# PT_2015_PB_MAIN_Rev1.net
KiCad netlist of a schematic drawn in EAGLE
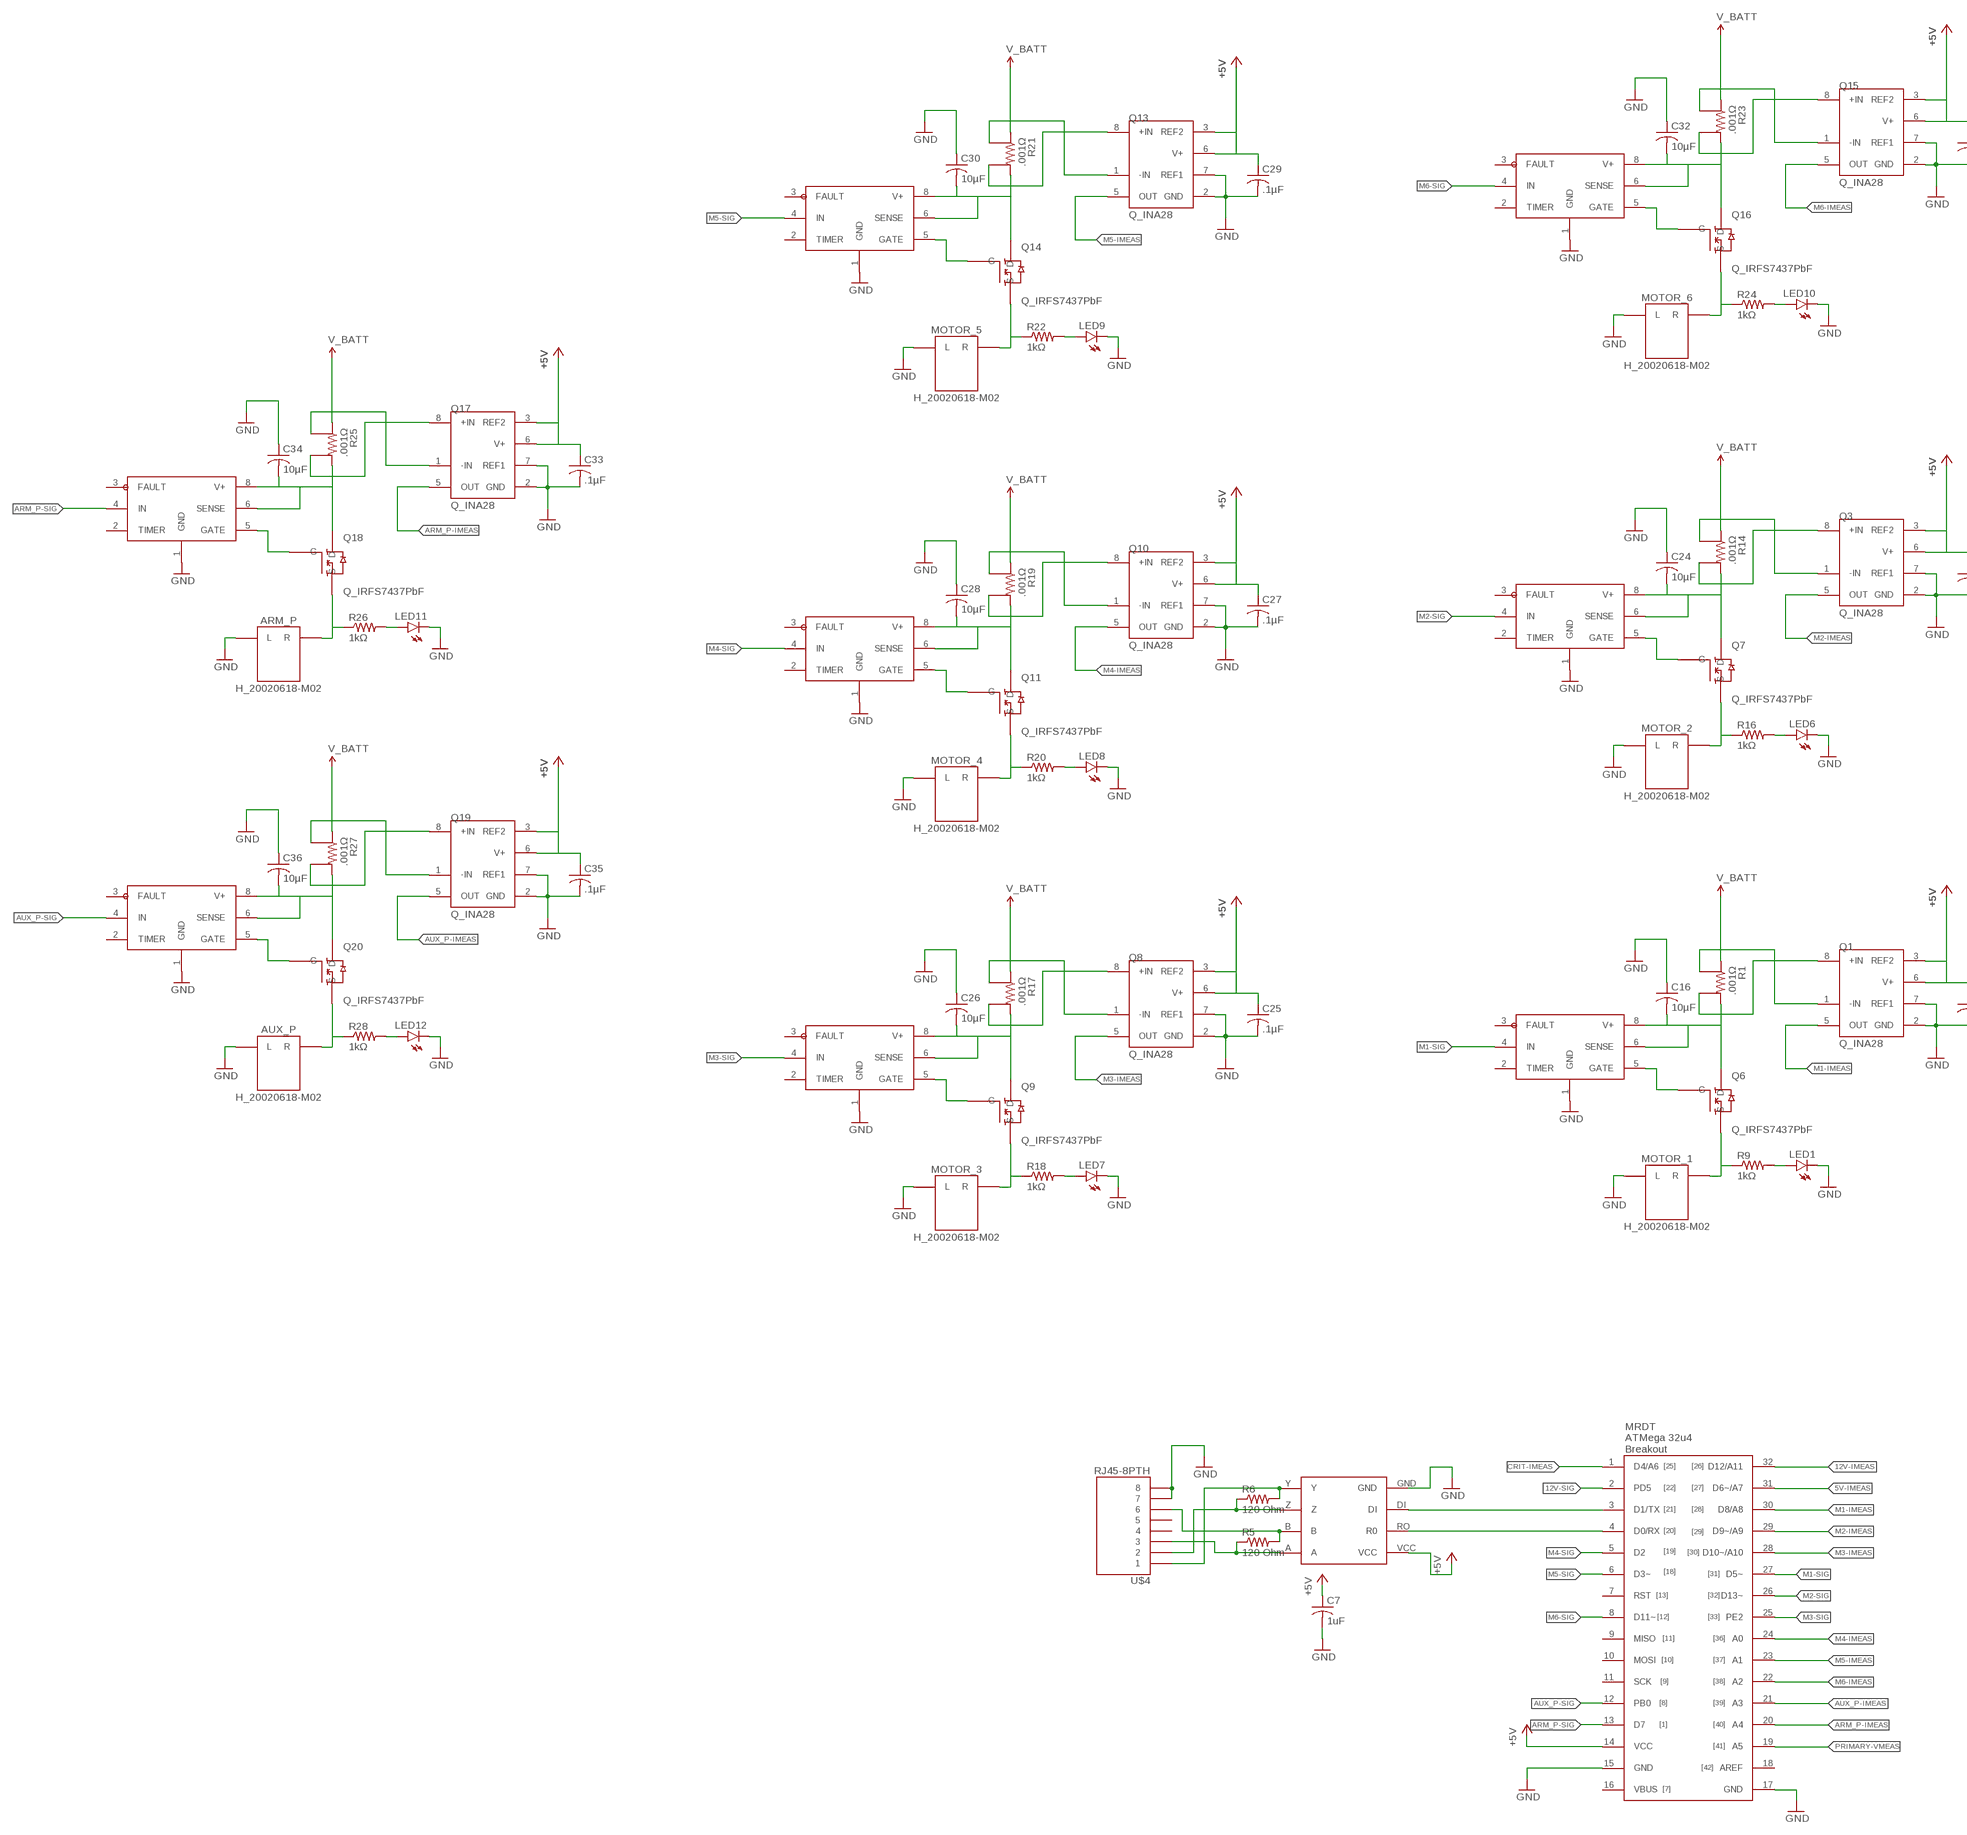
[diagram p0: schematic, sheet 1, part 1 of 2]
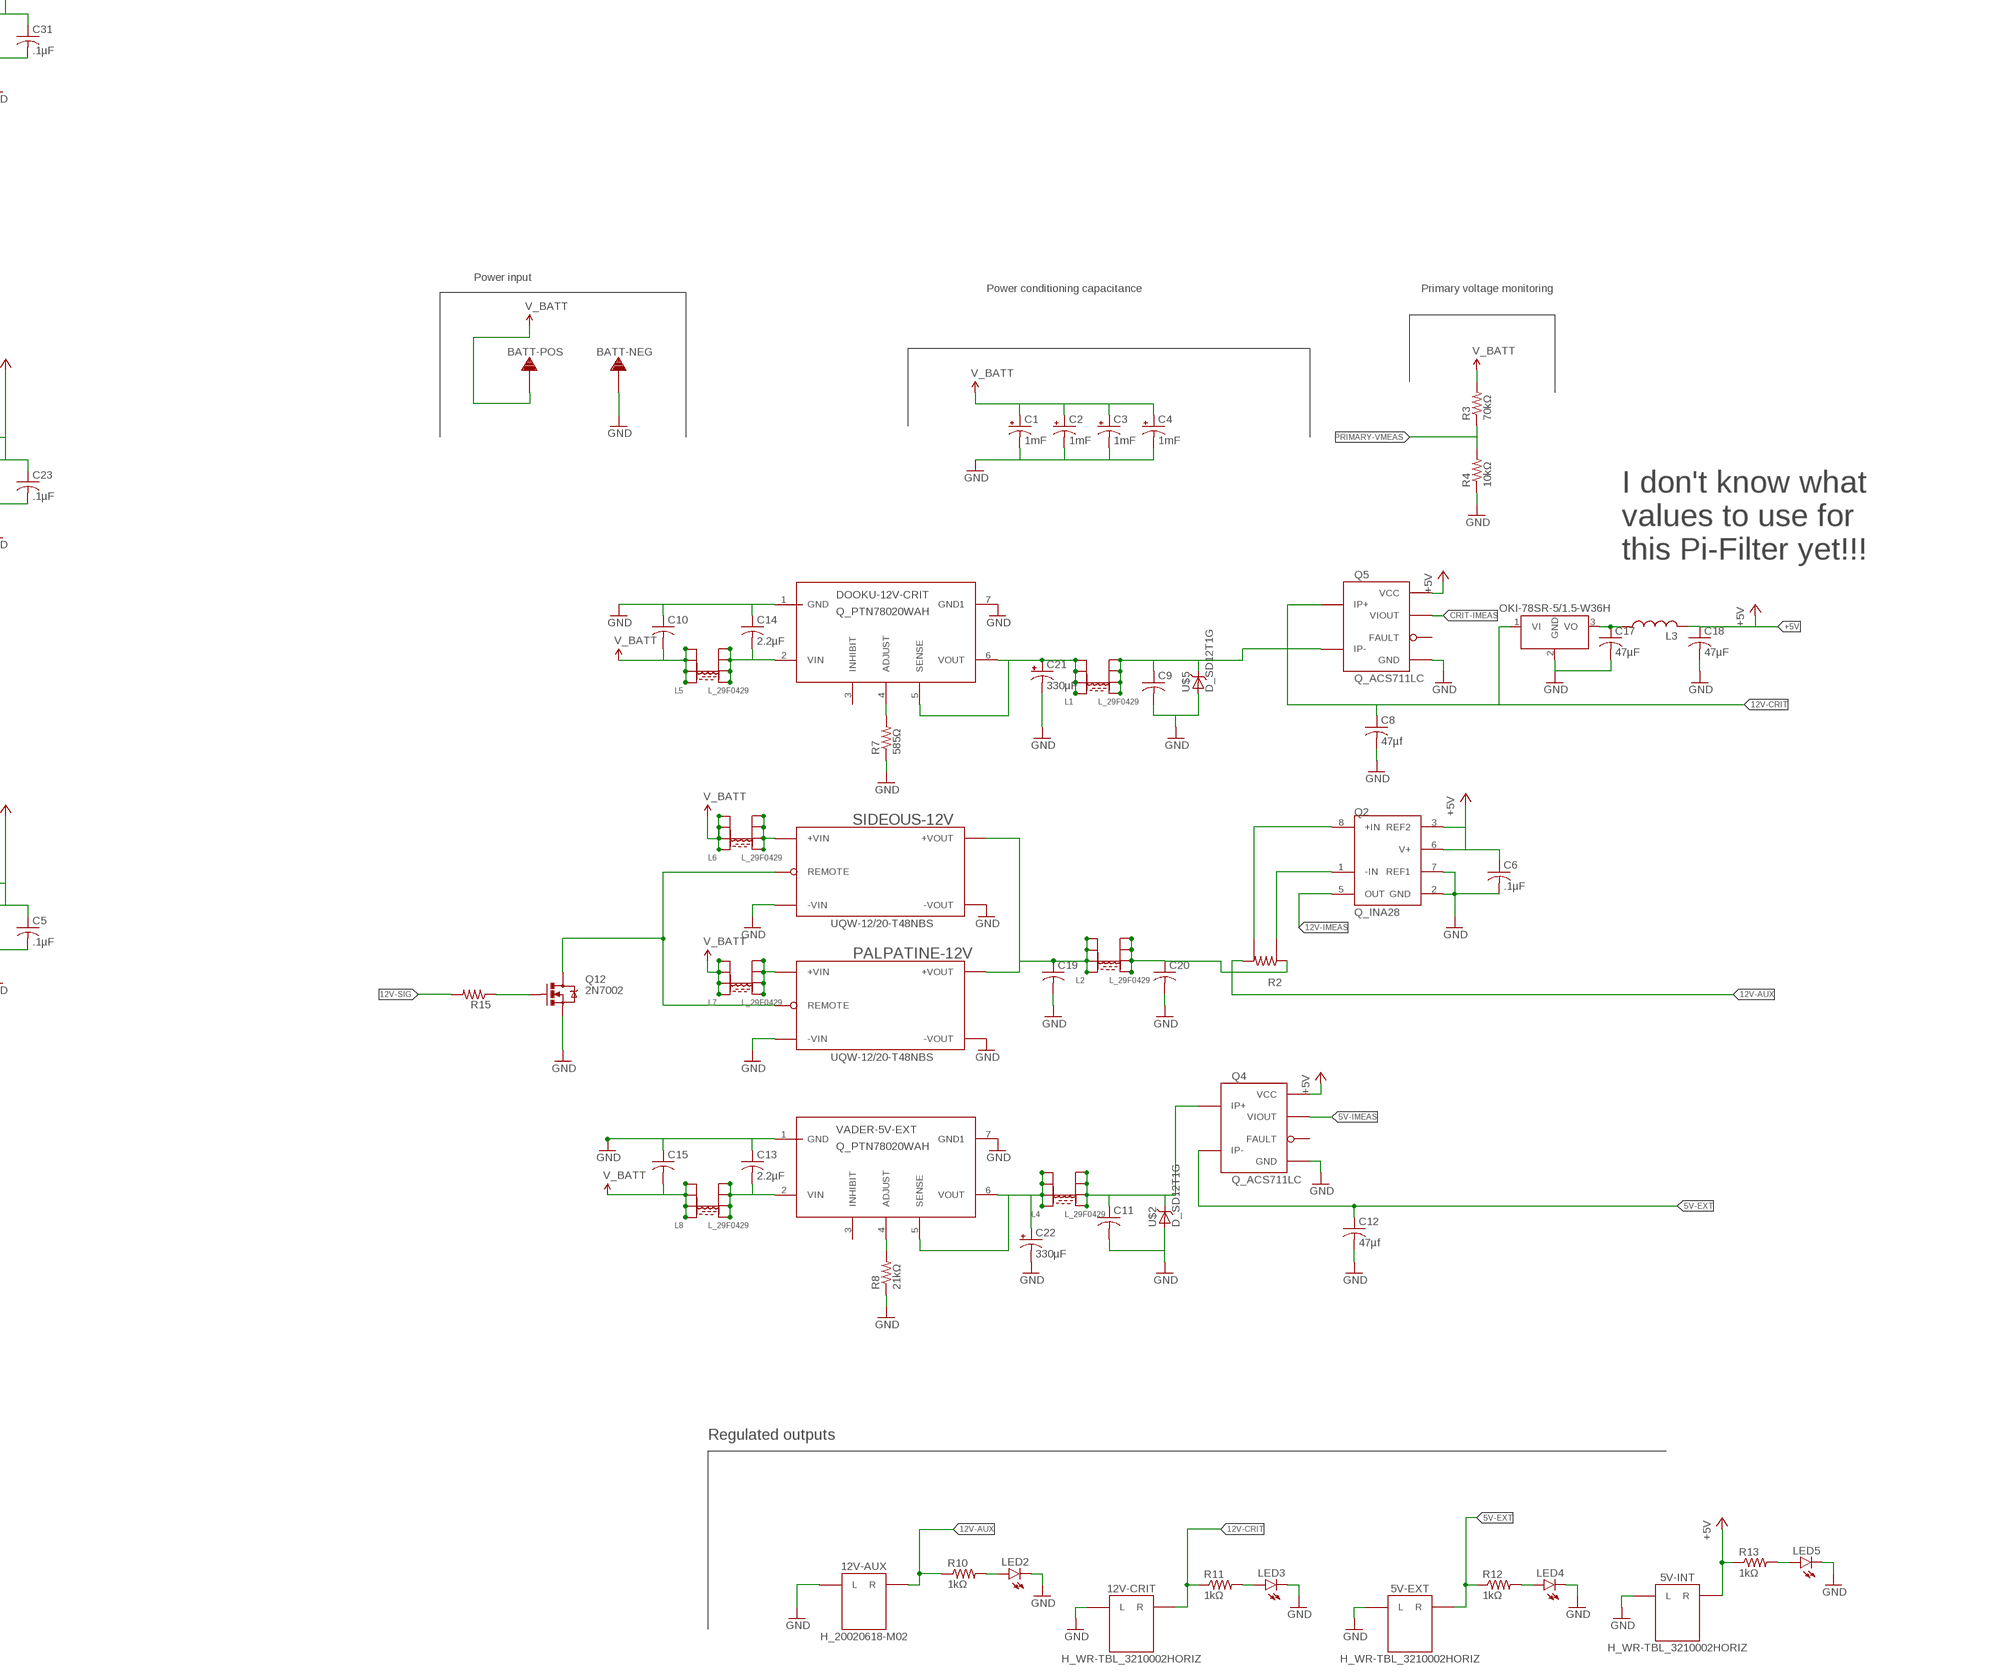
[diagram p1: schematic, sheet 1, part 2 of 2]

(export (version "E")
  (design (tool "Eeschema 10.0.6"))
  (components
    (comp (ref "5V-EXT")
      (value "H_WR-TBL_3210002HORIZ")
      (footprint "eagle-import:691322110002")
      (libsource (lib "eagle-import") (part "H_WR-TBL_3210002HORIZ"))
    )
    (comp (ref "5V-INT")
      (value "H_WR-TBL_3210002HORIZ")
      (footprint "eagle-import:691322110002")
      (libsource (lib "eagle-import") (part "H_WR-TBL_3210002HORIZ"))
    )
    (comp (ref "12V-AUX")
      (value "H_20020618-M02")
      (footprint "eagle-import:20020618-M02")
      (libsource (lib "eagle-import") (part "H_20020618-M02"))
    )
    (comp (ref "12V-CRIT")
      (value "H_WR-TBL_3210002HORIZ")
      (footprint "eagle-import:691322110002")
      (libsource (lib "eagle-import") (part "H_WR-TBL_3210002HORIZ"))
    )
    (comp (ref "ARM_P")
      (value "H_20020618-M02")
      (footprint "eagle-import:20020618-M02")
      (libsource (lib "eagle-import") (part "H_20020618-M02"))
    )
    (comp (ref "AUX_P")
      (value "H_20020618-M02")
      (footprint "eagle-import:20020618-M02")
      (libsource (lib "eagle-import") (part "H_20020618-M02"))
    )
    (comp (ref "BATT-NEG")
      (value "TERMINAL_HOLE")
      (footprint "eagle-import:LARGE_TERMINAL_HOLE")
      (libsource (lib "eagle-import") (part "TERMINAL_HOLE"))
    )
    (comp (ref "BATT-POS")
      (value "TERMINAL_HOLE")
      (footprint "eagle-import:LARGE_TERMINAL_HOLE")
      (libsource (lib "eagle-import") (part "TERMINAL_HOLE"))
    )
    (comp (ref "C1")
      (value "1mF")
      (footprint "eagle-import:C_12.5MM")
      (libsource (lib "eagle-import") (part "C_POL12.5MM_NORMAL"))
    )
    (comp (ref "C2")
      (value "1mF")
      (footprint "eagle-import:C_12.5MM")
      (libsource (lib "eagle-import") (part "C_POL12.5MM_NORMAL"))
    )
    (comp (ref "C3")
      (value "1mF")
      (footprint "eagle-import:C_12.5MM")
      (libsource (lib "eagle-import") (part "C_POL12.5MM_NORMAL"))
    )
    (comp (ref "C4")
      (value "1mF")
      (footprint "eagle-import:C_12.5MM")
      (libsource (lib "eagle-import") (part "C_POL12.5MM_NORMAL"))
    )
    (comp (ref "C5")
      (value ".1µF")
      (footprint "eagle-import:C1206")
      (libsource (lib "eagle-import") (part "C-USC1206"))
    )
    (comp (ref "C6")
      (value ".1µF")
      (footprint "eagle-import:C1206")
      (libsource (lib "eagle-import") (part "C-USC1206"))
    )
    (comp (ref "C7")
      (value "1uF")
      (footprint "eagle-import:C1206")
      (libsource (lib "eagle-import") (part "C-USC1206"))
    )
    (comp (ref "C8")
      (value "47µf")
      (footprint "eagle-import:C1206")
      (libsource (lib "eagle-import") (part "C-USC1206"))
    )
    (comp (ref "C9")
      (value "C-USC1206")
      (footprint "eagle-import:C1206")
      (libsource (lib "eagle-import") (part "C-USC1206"))
    )
    (comp (ref "C10")
      (value "C-USC1206")
      (footprint "eagle-import:C1206")
      (libsource (lib "eagle-import") (part "C-USC1206"))
    )
    (comp (ref "C11")
      (value "C-USC1206")
      (footprint "eagle-import:C1206")
      (libsource (lib "eagle-import") (part "C-USC1206"))
    )
    (comp (ref "C12")
      (value "47µf")
      (footprint "eagle-import:C1206")
      (libsource (lib "eagle-import") (part "C-USC1206"))
    )
    (comp (ref "C13")
      (value "2.2µF")
      (footprint "eagle-import:C1206")
      (libsource (lib "eagle-import") (part "C-USC1206"))
    )
    (comp (ref "C14")
      (value "2.2µF")
      (footprint "eagle-import:C1206")
      (libsource (lib "eagle-import") (part "C-USC1206"))
    )
    (comp (ref "C15")
      (value "C-USC1206")
      (footprint "eagle-import:C1206")
      (libsource (lib "eagle-import") (part "C-USC1206"))
    )
    (comp (ref "C16")
      (value "10µF")
      (footprint "eagle-import:C1206")
      (libsource (lib "eagle-import") (part "C-USC1206"))
    )
    (comp (ref "C17")
      (value "47µF")
      (footprint "eagle-import:C1206")
      (libsource (lib "eagle-import") (part "C-USC1206"))
    )
    (comp (ref "C18")
      (value "47µF")
      (footprint "eagle-import:C1206")
      (libsource (lib "eagle-import") (part "C-USC1206"))
    )
    (comp (ref "C19")
      (value "C-USC1206")
      (footprint "eagle-import:C1206")
      (libsource (lib "eagle-import") (part "C-USC1206"))
    )
    (comp (ref "C20")
      (value "C-USC1206")
      (footprint "eagle-import:C1206")
      (libsource (lib "eagle-import") (part "C-USC1206"))
    )
    (comp (ref "C21")
      (value "330µF")
      (footprint "eagle-import:E5-8,5")
      (libsource (lib "eagle-import") (part "CPOL-USE5-8.5"))
    )
    (comp (ref "C22")
      (value "330µF")
      (footprint "eagle-import:E5-8,5")
      (libsource (lib "eagle-import") (part "CPOL-USE5-8.5"))
    )
    (comp (ref "C23")
      (value ".1µF")
      (footprint "eagle-import:C1206")
      (libsource (lib "eagle-import") (part "C-USC1206"))
    )
    (comp (ref "C24")
      (value "10µF")
      (footprint "eagle-import:C1206")
      (libsource (lib "eagle-import") (part "C-USC1206"))
    )
    (comp (ref "C25")
      (value ".1µF")
      (footprint "eagle-import:C1206")
      (libsource (lib "eagle-import") (part "C-USC1206"))
    )
    (comp (ref "C26")
      (value "10µF")
      (footprint "eagle-import:C1206")
      (libsource (lib "eagle-import") (part "C-USC1206"))
    )
    (comp (ref "C27")
      (value ".1µF")
      (footprint "eagle-import:C1206")
      (libsource (lib "eagle-import") (part "C-USC1206"))
    )
    (comp (ref "C28")
      (value "10µF")
      (footprint "eagle-import:C1206")
      (libsource (lib "eagle-import") (part "C-USC1206"))
    )
    (comp (ref "C29")
      (value ".1µF")
      (footprint "eagle-import:C1206")
      (libsource (lib "eagle-import") (part "C-USC1206"))
    )
    (comp (ref "C30")
      (value "10µF")
      (footprint "eagle-import:C1206")
      (libsource (lib "eagle-import") (part "C-USC1206"))
    )
    (comp (ref "C31")
      (value ".1µF")
      (footprint "eagle-import:C1206")
      (libsource (lib "eagle-import") (part "C-USC1206"))
    )
    (comp (ref "C32")
      (value "10µF")
      (footprint "eagle-import:C1206")
      (libsource (lib "eagle-import") (part "C-USC1206"))
    )
    (comp (ref "C33")
      (value ".1µF")
      (footprint "eagle-import:C1206")
      (libsource (lib "eagle-import") (part "C-USC1206"))
    )
    (comp (ref "C34")
      (value "10µF")
      (footprint "eagle-import:C1206")
      (libsource (lib "eagle-import") (part "C-USC1206"))
    )
    (comp (ref "C35")
      (value ".1µF")
      (footprint "eagle-import:C1206")
      (libsource (lib "eagle-import") (part "C-USC1206"))
    )
    (comp (ref "C36")
      (value "10µF")
      (footprint "eagle-import:C1206")
      (libsource (lib "eagle-import") (part "C-USC1206"))
    )
    (comp (ref "DOOKU-12V-CRIT")
      (value "Q_PTN78020WAH")
      (footprint "eagle-import:R_PDSS-T7")
      (libsource (lib "eagle-import") (part "Q_PTN78020"))
    )
    (comp (ref "L1")
      (value "L_29F0429")
      (footprint "eagle-import:L_29F0429")
      (libsource (lib "eagle-import") (part "L_29F0429"))
    )
    (comp (ref "L2")
      (value "L_29F0429")
      (footprint "eagle-import:L_29F0429")
      (libsource (lib "eagle-import") (part "L_29F0429"))
    )
    (comp (ref "L3")
      (value "L-USL3216C")
      (footprint "eagle-import:L3216C")
      (libsource (lib "eagle-import") (part "L-USL3216C"))
    )
    (comp (ref "L4")
      (value "L_29F0429")
      (footprint "eagle-import:L_29F0429")
      (libsource (lib "eagle-import") (part "L_29F0429"))
    )
    (comp (ref "L5")
      (value "L_29F0429")
      (footprint "eagle-import:L_29F0429")
      (libsource (lib "eagle-import") (part "L_29F0429"))
    )
    (comp (ref "L6")
      (value "L_29F0429")
      (footprint "eagle-import:L_29F0429")
      (libsource (lib "eagle-import") (part "L_29F0429"))
    )
    (comp (ref "L7")
      (value "L_29F0429")
      (footprint "eagle-import:L_29F0429")
      (libsource (lib "eagle-import") (part "L_29F0429"))
    )
    (comp (ref "L8")
      (value "L_29F0429")
      (footprint "eagle-import:L_29F0429")
      (libsource (lib "eagle-import") (part "L_29F0429"))
    )
    (comp (ref "LED1")
      (value "LED1206")
      (footprint "eagle-import:LED-1206")
      (libsource (lib "eagle-import") (part "LED1206"))
    )
    (comp (ref "LED2")
      (value "LED1206")
      (footprint "eagle-import:LED-1206")
      (libsource (lib "eagle-import") (part "LED1206"))
    )
    (comp (ref "LED3")
      (value "LED1206")
      (footprint "eagle-import:LED-1206")
      (libsource (lib "eagle-import") (part "LED1206"))
    )
    (comp (ref "LED4")
      (value "LED1206")
      (footprint "eagle-import:LED-1206")
      (libsource (lib "eagle-import") (part "LED1206"))
    )
    (comp (ref "LED5")
      (value "LED1206")
      (footprint "eagle-import:LED-1206")
      (libsource (lib "eagle-import") (part "LED1206"))
    )
    (comp (ref "LED6")
      (value "LED1206")
      (footprint "eagle-import:LED-1206")
      (libsource (lib "eagle-import") (part "LED1206"))
    )
    (comp (ref "LED7")
      (value "LED1206")
      (footprint "eagle-import:LED-1206")
      (libsource (lib "eagle-import") (part "LED1206"))
    )
    (comp (ref "LED8")
      (value "LED1206")
      (footprint "eagle-import:LED-1206")
      (libsource (lib "eagle-import") (part "LED1206"))
    )
    (comp (ref "LED9")
      (value "LED1206")
      (footprint "eagle-import:LED-1206")
      (libsource (lib "eagle-import") (part "LED1206"))
    )
    (comp (ref "LED10")
      (value "LED1206")
      (footprint "eagle-import:LED-1206")
      (libsource (lib "eagle-import") (part "LED1206"))
    )
    (comp (ref "LED11")
      (value "LED1206")
      (footprint "eagle-import:LED-1206")
      (libsource (lib "eagle-import") (part "LED1206"))
    )
    (comp (ref "LED12")
      (value "LED1206")
      (footprint "eagle-import:LED-1206")
      (libsource (lib "eagle-import") (part "LED1206"))
    )
    (comp (ref "MOTOR_1")
      (value "H_20020618-M02")
      (footprint "eagle-import:20020618-M02")
      (libsource (lib "eagle-import") (part "H_20020618-M02"))
    )
    (comp (ref "MOTOR_2")
      (value "H_20020618-M02")
      (footprint "eagle-import:20020618-M02")
      (libsource (lib "eagle-import") (part "H_20020618-M02"))
    )
    (comp (ref "MOTOR_3")
      (value "H_20020618-M02")
      (footprint "eagle-import:20020618-M02")
      (libsource (lib "eagle-import") (part "H_20020618-M02"))
    )
    (comp (ref "MOTOR_4")
      (value "H_20020618-M02")
      (footprint "eagle-import:20020618-M02")
      (libsource (lib "eagle-import") (part "H_20020618-M02"))
    )
    (comp (ref "MOTOR_5")
      (value "H_20020618-M02")
      (footprint "eagle-import:20020618-M02")
      (libsource (lib "eagle-import") (part "H_20020618-M02"))
    )
    (comp (ref "MOTOR_6")
      (value "H_20020618-M02")
      (footprint "eagle-import:20020618-M02")
      (libsource (lib "eagle-import") (part "H_20020618-M02"))
    )
    (comp (ref "OKI-78SR-5/1.5-W36H")
      (value "Q_OKI-78SR")
      (footprint "eagle-import:OKI-78SRH")
      (libsource (lib "eagle-import") (part "Q_OKI-78SR"))
    )
    (comp (ref "PALPATINE-12V")
      (value "UQW-12/20-T48NBS")
      (footprint "eagle-import:U-T48-QB-NO_TRIM")
      (libsource (lib "eagle-import") (part "UQW-12/20-T48NBS"))
    )
    (comp (ref "Q1")
      (value "Q_INA28")
      (footprint "eagle-import:SOIC8")
      (libsource (lib "eagle-import") (part "Q_INA28"))
    )
    (comp (ref "Q2")
      (value "Q_INA28")
      (footprint "eagle-import:SOIC8")
      (libsource (lib "eagle-import") (part "Q_INA28"))
    )
    (comp (ref "Q3")
      (value "Q_INA28")
      (footprint "eagle-import:SOIC8")
      (libsource (lib "eagle-import") (part "Q_INA28"))
    )
    (comp (ref "Q4")
      (value "Q_ACS711LC")
      (footprint "eagle-import:SOIC8_ACS711")
      (libsource (lib "eagle-import") (part "Q_ACS711LC"))
    )
    (comp (ref "Q5")
      (value "Q_ACS711LC")
      (footprint "eagle-import:SOIC8_ACS711")
      (libsource (lib "eagle-import") (part "Q_ACS711LC"))
    )
    (comp (ref "Q6")
      (value "Q_IRFS7437PbF")
      (footprint "eagle-import:D2PACK")
      (libsource (lib "eagle-import") (part "Q_IRF7437SMD"))
    )
    (comp (ref "Q7")
      (value "Q_IRFS7437PbF")
      (footprint "eagle-import:D2PACK")
      (libsource (lib "eagle-import") (part "Q_IRF7437SMD"))
    )
    (comp (ref "Q8")
      (value "Q_INA28")
      (footprint "eagle-import:SOIC8")
      (libsource (lib "eagle-import") (part "Q_INA28"))
    )
    (comp (ref "Q9")
      (value "Q_IRFS7437PbF")
      (footprint "eagle-import:D2PACK")
      (libsource (lib "eagle-import") (part "Q_IRF7437SMD"))
    )
    (comp (ref "Q10")
      (value "Q_INA28")
      (footprint "eagle-import:SOIC8")
      (libsource (lib "eagle-import") (part "Q_INA28"))
    )
    (comp (ref "Q11")
      (value "Q_IRFS7437PbF")
      (footprint "eagle-import:D2PACK")
      (libsource (lib "eagle-import") (part "Q_IRF7437SMD"))
    )
    (comp (ref "Q12")
      (value "2N7002")
      (footprint "eagle-import:SOT323")
      (libsource (lib "eagle-import") (part "MOSFET-NCHANNEL2N7002PW"))
    )
    (comp (ref "Q13")
      (value "Q_INA28")
      (footprint "eagle-import:SOIC8")
      (libsource (lib "eagle-import") (part "Q_INA28"))
    )
    (comp (ref "Q14")
      (value "Q_IRFS7437PbF")
      (footprint "eagle-import:D2PACK")
      (libsource (lib "eagle-import") (part "Q_IRF7437SMD"))
    )
    (comp (ref "Q15")
      (value "Q_INA28")
      (footprint "eagle-import:SOIC8")
      (libsource (lib "eagle-import") (part "Q_INA28"))
    )
    (comp (ref "Q16")
      (value "Q_IRFS7437PbF")
      (footprint "eagle-import:D2PACK")
      (libsource (lib "eagle-import") (part "Q_IRF7437SMD"))
    )
    (comp (ref "Q17")
      (value "Q_INA28")
      (footprint "eagle-import:SOIC8")
      (libsource (lib "eagle-import") (part "Q_INA28"))
    )
    (comp (ref "Q18")
      (value "Q_IRFS7437PbF")
      (footprint "eagle-import:D2PACK")
      (libsource (lib "eagle-import") (part "Q_IRF7437SMD"))
    )
    (comp (ref "Q19")
      (value "Q_INA28")
      (footprint "eagle-import:SOIC8")
      (libsource (lib "eagle-import") (part "Q_INA28"))
    )
    (comp (ref "Q20")
      (value "Q_IRFS7437PbF")
      (footprint "eagle-import:D2PACK")
      (libsource (lib "eagle-import") (part "Q_IRF7437SMD"))
    )
    (comp (ref "R1")
      (value ".001Ω")
      (footprint "eagle-import:R_FC4L")
      (libsource (lib "eagle-import") (part "R_FC4L110R001JER"))
    )
    (comp (ref "R2")
      (value "R_FC4L110R001JER")
      (footprint "eagle-import:R_FC4L")
      (libsource (lib "eagle-import") (part "R_FC4L110R001JER"))
    )
    (comp (ref "R3")
      (value "70kΩ")
      (footprint "eagle-import:R1206")
      (libsource (lib "eagle-import") (part "R-US_R1206"))
    )
    (comp (ref "R4")
      (value "10kΩ")
      (footprint "eagle-import:R1206")
      (libsource (lib "eagle-import") (part "R-US_R1206"))
    )
    (comp (ref "R5")
      (value "120 Ohm")
      (footprint "eagle-import:1206")
      (libsource (lib "eagle-import") (part "RESISTOR1206"))
    )
    (comp (ref "R6")
      (value "120 Ohm")
      (footprint "eagle-import:1206")
      (libsource (lib "eagle-import") (part "RESISTOR1206"))
    )
    (comp (ref "R7")
      (value "585Ω")
      (footprint "eagle-import:R1206")
      (libsource (lib "eagle-import") (part "R-US_R1206"))
    )
    (comp (ref "R8")
      (value "21kΩ")
      (footprint "eagle-import:R1206")
      (libsource (lib "eagle-import") (part "R-US_R1206"))
    )
    (comp (ref "R9")
      (value "1kΩ")
      (footprint "eagle-import:1206")
      (libsource (lib "eagle-import") (part "RESISTOR1206"))
    )
    (comp (ref "R10")
      (value "1kΩ")
      (footprint "eagle-import:1206")
      (libsource (lib "eagle-import") (part "RESISTOR1206"))
    )
    (comp (ref "R11")
      (value "1kΩ")
      (footprint "eagle-import:1206")
      (libsource (lib "eagle-import") (part "RESISTOR1206"))
    )
    (comp (ref "R12")
      (value "1kΩ")
      (footprint "eagle-import:1206")
      (libsource (lib "eagle-import") (part "RESISTOR1206"))
    )
    (comp (ref "R13")
      (value "1kΩ")
      (footprint "eagle-import:1206")
      (libsource (lib "eagle-import") (part "RESISTOR1206"))
    )
    (comp (ref "R14")
      (value ".001Ω")
      (footprint "eagle-import:R_FC4L")
      (libsource (lib "eagle-import") (part "R_FC4L110R001JER"))
    )
    (comp (ref "R15")
      (value "R-US_R1206")
      (footprint "eagle-import:R1206")
      (libsource (lib "eagle-import") (part "R-US_R1206"))
    )
    (comp (ref "R16")
      (value "1kΩ")
      (footprint "eagle-import:1206")
      (libsource (lib "eagle-import") (part "RESISTOR1206"))
    )
    (comp (ref "R17")
      (value ".001Ω")
      (footprint "eagle-import:R_FC4L")
      (libsource (lib "eagle-import") (part "R_FC4L110R001JER"))
    )
    (comp (ref "R18")
      (value "1kΩ")
      (footprint "eagle-import:1206")
      (libsource (lib "eagle-import") (part "RESISTOR1206"))
    )
    (comp (ref "R19")
      (value ".001Ω")
      (footprint "eagle-import:R_FC4L")
      (libsource (lib "eagle-import") (part "R_FC4L110R001JER"))
    )
    (comp (ref "R20")
      (value "1kΩ")
      (footprint "eagle-import:1206")
      (libsource (lib "eagle-import") (part "RESISTOR1206"))
    )
    (comp (ref "R21")
      (value ".001Ω")
      (footprint "eagle-import:R_FC4L")
      (libsource (lib "eagle-import") (part "R_FC4L110R001JER"))
    )
    (comp (ref "R22")
      (value "1kΩ")
      (footprint "eagle-import:1206")
      (libsource (lib "eagle-import") (part "RESISTOR1206"))
    )
    (comp (ref "R23")
      (value ".001Ω")
      (footprint "eagle-import:R_FC4L")
      (libsource (lib "eagle-import") (part "R_FC4L110R001JER"))
    )
    (comp (ref "R24")
      (value "1kΩ")
      (footprint "eagle-import:1206")
      (libsource (lib "eagle-import") (part "RESISTOR1206"))
    )
    (comp (ref "R25")
      (value ".001Ω")
      (footprint "eagle-import:R_FC4L")
      (libsource (lib "eagle-import") (part "R_FC4L110R001JER"))
    )
    (comp (ref "R26")
      (value "1kΩ")
      (footprint "eagle-import:1206")
      (libsource (lib "eagle-import") (part "RESISTOR1206"))
    )
    (comp (ref "R27")
      (value ".001Ω")
      (footprint "eagle-import:R_FC4L")
      (libsource (lib "eagle-import") (part "R_FC4L110R001JER"))
    )
    (comp (ref "R28")
      (value "1kΩ")
      (footprint "eagle-import:1206")
      (libsource (lib "eagle-import") (part "RESISTOR1206"))
    )
    (comp (ref "SIDEOUS-12V")
      (value "UQW-12/20-T48NBS")
      (footprint "eagle-import:U-T48-QB-NO_TRIM")
      (libsource (lib "eagle-import") (part "UQW-12/20-T48NBS"))
    )
    (comp (ref "U$1")
      (value "32U4_BREAKOUT")
      (footprint "eagle-import:32U4_MCU_DIP")
      (libsource (lib "eagle-import") (part "32U4_BREAKOUT"))
    )
    (comp (ref "U$2")
      (value "D_SD12T1G")
      (footprint "eagle-import:SOD-323")
      (libsource (lib "eagle-import") (part "D_SD12T1G"))
    )
    (comp (ref "U$3")
      (value "MAX3077")
      (footprint "eagle-import:MAX3070E")
      (libsource (lib "eagle-import") (part "MAX3077"))
    )
    (comp (ref "U$4")
      (value "RJ45-8PTH")
      (footprint "eagle-import:RJ45-8")
      (libsource (lib "eagle-import") (part "RJ45-8PTH"))
    )
    (comp (ref "U$5")
      (value "D_SD12T1G")
      (footprint "eagle-import:SOD-323")
      (libsource (lib "eagle-import") (part "D_SD12T1G"))
    )
    (comp (ref "U$6")
      (value "LT1910")
      (footprint "eagle-import:SO8")
      (libsource (lib "eagle-import") (part "LT1910"))
    )
    (comp (ref "U$7")
      (value "LT1910")
      (footprint "eagle-import:SO8")
      (libsource (lib "eagle-import") (part "LT1910"))
    )
    (comp (ref "U$8")
      (value "LT1910")
      (footprint "eagle-import:SO8")
      (libsource (lib "eagle-import") (part "LT1910"))
    )
    (comp (ref "U$9")
      (value "LT1910")
      (footprint "eagle-import:SO8")
      (libsource (lib "eagle-import") (part "LT1910"))
    )
    (comp (ref "U$10")
      (value "LT1910")
      (footprint "eagle-import:SO8")
      (libsource (lib "eagle-import") (part "LT1910"))
    )
    (comp (ref "U$11")
      (value "LT1910")
      (footprint "eagle-import:SO8")
      (libsource (lib "eagle-import") (part "LT1910"))
    )
    (comp (ref "U$12")
      (value "LT1910")
      (footprint "eagle-import:SO8")
      (libsource (lib "eagle-import") (part "LT1910"))
    )
    (comp (ref "U$13")
      (value "LT1910")
      (footprint "eagle-import:SO8")
      (libsource (lib "eagle-import") (part "LT1910"))
    )
    (comp (ref "VADER-5V-EXT")
      (value "Q_PTN78020WAH")
      (footprint "eagle-import:R_PDSS-T7")
      (libsource (lib "eagle-import") (part "Q_PTN78020"))
    )
  )
  (nets
    (net (code "1") (name "+5V") (class "Default")
      (node (ref "5V-INT") (pin "R") (pinfunction "R_R") (pintype "bidirectional"))
      (node (ref "C18") (pin "1") (pinfunction "1_1") (pintype "passive"))
      (node (ref "C23") (pin "1") (pinfunction "1_1") (pintype "passive"))
      (node (ref "C25") (pin "1") (pinfunction "1_1") (pintype "passive"))
      (node (ref "C27") (pin "1") (pinfunction "1_1") (pintype "passive"))
      (node (ref "C29") (pin "1") (pinfunction "1_1") (pintype "passive"))
      (node (ref "C31") (pin "1") (pinfunction "1_1") (pintype "passive"))
      (node (ref "C33") (pin "1") (pinfunction "1_1") (pintype "passive"))
      (node (ref "C35") (pin "1") (pinfunction "1_1") (pintype "passive"))
      (node (ref "C5") (pin "1") (pinfunction "1_1") (pintype "passive"))
      (node (ref "C6") (pin "1") (pinfunction "1_1") (pintype "passive"))
      (node (ref "C7") (pin "1") (pinfunction "1_1") (pintype "passive"))
      (node (ref "L3") (pin "2") (pinfunction "2_2") (pintype "passive"))
      (node (ref "Q1") (pin "3") (pinfunction "REF2_3") (pintype "bidirectional"))
      (node (ref "Q1") (pin "6") (pinfunction "V+_6") (pintype "bidirectional"))
      (node (ref "Q10") (pin "3") (pinfunction "REF2_3") (pintype "bidirectional"))
      (node (ref "Q10") (pin "6") (pinfunction "V+_6") (pintype "bidirectional"))
      (node (ref "Q13") (pin "3") (pinfunction "REF2_3") (pintype "bidirectional"))
      (node (ref "Q13") (pin "6") (pinfunction "V+_6") (pintype "bidirectional"))
      (node (ref "Q15") (pin "3") (pinfunction "REF2_3") (pintype "bidirectional"))
      (node (ref "Q15") (pin "6") (pinfunction "V+_6") (pintype "bidirectional"))
      (node (ref "Q17") (pin "3") (pinfunction "REF2_3") (pintype "bidirectional"))
      (node (ref "Q17") (pin "6") (pinfunction "V+_6") (pintype "bidirectional"))
      (node (ref "Q19") (pin "3") (pinfunction "REF2_3") (pintype "bidirectional"))
      (node (ref "Q19") (pin "6") (pinfunction "V+_6") (pintype "bidirectional"))
      (node (ref "Q2") (pin "3") (pinfunction "REF2_3") (pintype "bidirectional"))
      (node (ref "Q2") (pin "6") (pinfunction "V+_6") (pintype "bidirectional"))
      (node (ref "Q3") (pin "3") (pinfunction "REF2_3") (pintype "bidirectional"))
      (node (ref "Q3") (pin "6") (pinfunction "V+_6") (pintype "bidirectional"))
      (node (ref "Q4") (pin "8") (pinfunction "VCC_8") (pintype "bidirectional"))
      (node (ref "Q5") (pin "8") (pinfunction "VCC_8") (pintype "bidirectional"))
      (node (ref "Q8") (pin "3") (pinfunction "REF2_3") (pintype "bidirectional"))
      (node (ref "Q8") (pin "6") (pinfunction "V+_6") (pintype "bidirectional"))
      (node (ref "R13") (pin "1") (pinfunction "1_1") (pintype "passive"))
      (node (ref "U$1") (pin "14") (pinfunction "VCC_14") (pintype "bidirectional"))
      (node (ref "U$3") (pin "VCC") (pinfunction "VCC_VCC") (pintype "bidirectional"))
    )
    (net (code "2") (name "5V-EXT") (class "Default")
      (node (ref "5V-EXT") (pin "R") (pinfunction "R_R") (pintype "bidirectional"))
      (node (ref "C12") (pin "1") (pinfunction "1_1") (pintype "passive"))
      (node (ref "Q4") (pin "4") (pinfunction "IP-_4") (pintype "bidirectional"))
      (node (ref "R12") (pin "1") (pinfunction "1_1") (pintype "passive"))
    )
    (net (code "3") (name "5V-IMEAS") (class "Default")
      (node (ref "Q4") (pin "7") (pinfunction "VIOUT_7") (pintype "bidirectional"))
      (node (ref "U$1") (pin "31") (pinfunction "D6~{/A7}_31") (pintype "bidirectional"))
    )
    (net (code "4") (name "12V-AUX") (class "Default")
      (node (ref "12V-AUX") (pin "R1") (pinfunction "R_R1") (pintype "bidirectional"))
      (node (ref "12V-AUX") (pin "R2") (pinfunction "R_R2") (pintype "bidirectional"))
      (node (ref "R10") (pin "1") (pinfunction "1_1") (pintype "passive"))
      (node (ref "R2") (pin "2") (pinfunction "2_2") (pintype "passive"))
    )
    (net (code "5") (name "12V-CRIT") (class "Default")
      (node (ref "12V-CRIT") (pin "R") (pinfunction "R_R") (pintype "bidirectional"))
      (node (ref "C8") (pin "1") (pinfunction "1_1") (pintype "passive"))
      (node (ref "OKI-78SR-5/1.5-W36H") (pin "1") (pinfunction "VI_1") (pintype "bidirectional"))
      (node (ref "Q5") (pin "1") (pinfunction "IP+_1") (pintype "bidirectional"))
      (node (ref "R11") (pin "1") (pinfunction "1_1") (pintype "passive"))
    )
    (net (code "6") (name "12V-IMEAS") (class "Default")
      (node (ref "Q2") (pin "5") (pinfunction "OUT_5") (pintype "bidirectional"))
      (node (ref "U$1") (pin "32") (pinfunction "D12/A11_32") (pintype "bidirectional"))
    )
    (net (code "7") (name "12V-SIG") (class "Default")
      (node (ref "R15") (pin "2") (pinfunction "2_2") (pintype "passive"))
      (node (ref "U$1") (pin "2") (pinfunction "PD5_2") (pintype "bidirectional"))
    )
    (net (code "8") (name "ARM_P-IMEAS") (class "Default")
      (node (ref "Q17") (pin "5") (pinfunction "OUT_5") (pintype "bidirectional"))
      (node (ref "U$1") (pin "20") (pinfunction "A4_20") (pintype "bidirectional"))
    )
    (net (code "9") (name "ARM_P-SIG") (class "Default")
      (node (ref "U$1") (pin "13") (pinfunction "D7_13") (pintype "bidirectional"))
      (node (ref "U$12") (pin "4") (pinfunction "IN_4") (pintype "bidirectional"))
    )
    (net (code "10") (name "AUX_P-IMEAS") (class "Default")
      (node (ref "Q19") (pin "5") (pinfunction "OUT_5") (pintype "bidirectional"))
      (node (ref "U$1") (pin "21") (pinfunction "A3_21") (pintype "bidirectional"))
    )
    (net (code "11") (name "AUX_P-SIG") (class "Default")
      (node (ref "U$1") (pin "12") (pinfunction "PB0_12") (pintype "bidirectional"))
      (node (ref "U$13") (pin "4") (pinfunction "IN_4") (pintype "bidirectional"))
    )
    (net (code "12") (name "CRIT-IMEAS") (class "Default")
      (node (ref "Q5") (pin "7") (pinfunction "VIOUT_7") (pintype "bidirectional"))
      (node (ref "U$1") (pin "1") (pinfunction "D4/A6_1") (pintype "bidirectional"))
    )
    (net (code "13") (name "GND") (class "Default")
      (node (ref "12V-AUX") (pin "L1") (pinfunction "L_L1") (pintype "bidirectional"))
      (node (ref "12V-AUX") (pin "L2") (pinfunction "L_L2") (pintype "bidirectional"))
      (node (ref "12V-CRIT") (pin "L") (pinfunction "L_L") (pintype "bidirectional"))
      (node (ref "5V-EXT") (pin "L") (pinfunction "L_L") (pintype "bidirectional"))
      (node (ref "5V-INT") (pin "L") (pinfunction "L_L") (pintype "bidirectional"))
      (node (ref "ARM_P") (pin "L1") (pinfunction "L_L1") (pintype "bidirectional"))
      (node (ref "ARM_P") (pin "L2") (pinfunction "L_L2") (pintype "bidirectional"))
      (node (ref "AUX_P") (pin "L1") (pinfunction "L_L1") (pintype "bidirectional"))
      (node (ref "AUX_P") (pin "L2") (pinfunction "L_L2") (pintype "bidirectional"))
      (node (ref "BATT-NEG") (pin "P$1") (pinfunction "P$1_P$1") (pintype "bidirectional"))
      (node (ref "C1") (pin "-") (pinfunction "-_-") (pintype "passive"))
      (node (ref "C10") (pin "1") (pinfunction "1_1") (pintype "passive"))
      (node (ref "C11") (pin "2") (pinfunction "2_2") (pintype "passive"))
      (node (ref "C12") (pin "2") (pinfunction "2_2") (pintype "passive"))
      (node (ref "C13") (pin "1") (pinfunction "1_1") (pintype "passive"))
      (node (ref "C14") (pin "1") (pinfunction "1_1") (pintype "passive"))
      (node (ref "C15") (pin "1") (pinfunction "1_1") (pintype "passive"))
      (node (ref "C16") (pin "1") (pinfunction "1_1") (pintype "passive"))
      (node (ref "C17") (pin "2") (pinfunction "2_2") (pintype "passive"))
      (node (ref "C18") (pin "2") (pinfunction "2_2") (pintype "passive"))
      (node (ref "C19") (pin "2") (pinfunction "2_2") (pintype "passive"))
      (node (ref "C2") (pin "-") (pinfunction "-_-") (pintype "passive"))
      (node (ref "C20") (pin "2") (pinfunction "2_2") (pintype "passive"))
      (node (ref "C21") (pin "-") (pinfunction "-_-") (pintype "passive"))
      (node (ref "C22") (pin "-") (pinfunction "-_-") (pintype "passive"))
      (node (ref "C23") (pin "2") (pinfunction "2_2") (pintype "passive"))
      (node (ref "C24") (pin "1") (pinfunction "1_1") (pintype "passive"))
      (node (ref "C25") (pin "2") (pinfunction "2_2") (pintype "passive"))
      (node (ref "C26") (pin "1") (pinfunction "1_1") (pintype "passive"))
      (node (ref "C27") (pin "2") (pinfunction "2_2") (pintype "passive"))
      (node (ref "C28") (pin "1") (pinfunction "1_1") (pintype "passive"))
      (node (ref "C29") (pin "2") (pinfunction "2_2") (pintype "passive"))
      (node (ref "C3") (pin "-") (pinfunction "-_-") (pintype "passive"))
      (node (ref "C30") (pin "1") (pinfunction "1_1") (pintype "passive"))
      (node (ref "C31") (pin "2") (pinfunction "2_2") (pintype "passive"))
      (node (ref "C32") (pin "1") (pinfunction "1_1") (pintype "passive"))
      (node (ref "C33") (pin "2") (pinfunction "2_2") (pintype "passive"))
      (node (ref "C34") (pin "1") (pinfunction "1_1") (pintype "passive"))
      (node (ref "C35") (pin "2") (pinfunction "2_2") (pintype "passive"))
      (node (ref "C36") (pin "1") (pinfunction "1_1") (pintype "passive"))
      (node (ref "C4") (pin "-") (pinfunction "-_-") (pintype "passive"))
      (node (ref "C5") (pin "2") (pinfunction "2_2") (pintype "passive"))
      (node (ref "C6") (pin "2") (pinfunction "2_2") (pintype "passive"))
      (node (ref "C7") (pin "2") (pinfunction "2_2") (pintype "passive"))
      (node (ref "C8") (pin "2") (pinfunction "2_2") (pintype "passive"))
      (node (ref "C9") (pin "2") (pinfunction "2_2") (pintype "passive"))
      (node (ref "DOOKU-12V-CRIT") (pin "1") (pinfunction "GND_1") (pintype "bidirectional"))
      (node (ref "DOOKU-12V-CRIT") (pin "7") (pinfunction "GND1_7") (pintype "bidirectional"))
      (node (ref "LED1") (pin "C") (pinfunction "C_C") (pintype "passive"))
      (node (ref "LED10") (pin "C") (pinfunction "C_C") (pintype "passive"))
      (node (ref "LED11") (pin "C") (pinfunction "C_C") (pintype "passive"))
      (node (ref "LED12") (pin "C") (pinfunction "C_C") (pintype "passive"))
      (node (ref "LED2") (pin "C") (pinfunction "C_C") (pintype "passive"))
      (node (ref "LED3") (pin "C") (pinfunction "C_C") (pintype "passive"))
      (node (ref "LED4") (pin "C") (pinfunction "C_C") (pintype "passive"))
      (node (ref "LED5") (pin "C") (pinfunction "C_C") (pintype "passive"))
      (node (ref "LED6") (pin "C") (pinfunction "C_C") (pintype "passive"))
      (node (ref "LED7") (pin "C") (pinfunction "C_C") (pintype "passive"))
      (node (ref "LED8") (pin "C") (pinfunction "C_C") (pintype "passive"))
      (node (ref "LED9") (pin "C") (pinfunction "C_C") (pintype "passive"))
      (node (ref "MOTOR_1") (pin "L1") (pinfunction "L_L1") (pintype "bidirectional"))
      (node (ref "MOTOR_1") (pin "L2") (pinfunction "L_L2") (pintype "bidirectional"))
      (node (ref "MOTOR_2") (pin "L1") (pinfunction "L_L1") (pintype "bidirectional"))
      (node (ref "MOTOR_2") (pin "L2") (pinfunction "L_L2") (pintype "bidirectional"))
      (node (ref "MOTOR_3") (pin "L1") (pinfunction "L_L1") (pintype "bidirectional"))
      (node (ref "MOTOR_3") (pin "L2") (pinfunction "L_L2") (pintype "bidirectional"))
      (node (ref "MOTOR_4") (pin "L1") (pinfunction "L_L1") (pintype "bidirectional"))
      (node (ref "MOTOR_4") (pin "L2") (pinfunction "L_L2") (pintype "bidirectional"))
      (node (ref "MOTOR_5") (pin "L1") (pinfunction "L_L1") (pintype "bidirectional"))
      (node (ref "MOTOR_5") (pin "L2") (pinfunction "L_L2") (pintype "bidirectional"))
      (node (ref "MOTOR_6") (pin "L1") (pinfunction "L_L1") (pintype "bidirectional"))
      (node (ref "MOTOR_6") (pin "L2") (pinfunction "L_L2") (pintype "bidirectional"))
      (node (ref "OKI-78SR-5/1.5-W36H") (pin "2") (pinfunction "GND_2") (pintype "bidirectional"))
      (node (ref "PALPATINE-12V") (pin "3") (pinfunction "-VIN_3") (pintype "bidirectional"))
      (node (ref "PALPATINE-12V") (pin "4") (pinfunction "-VOUT_4") (pintype "bidirectional"))
      (node (ref "Q1") (pin "2") (pinfunction "GND_2") (pintype "bidirectional"))
      (node (ref "Q1") (pin "7") (pinfunction "REF1_7") (pintype "bidirectional"))
      (node (ref "Q10") (pin "2") (pinfunction "GND_2") (pintype "bidirectional"))
      (node (ref "Q10") (pin "7") (pinfunction "REF1_7") (pintype "bidirectional"))
      (node (ref "Q12") (pin "2") (pinfunction "S_2") (pintype "passive"))
      (node (ref "Q13") (pin "2") (pinfunction "GND_2") (pintype "bidirectional"))
      (node (ref "Q13") (pin "7") (pinfunction "REF1_7") (pintype "bidirectional"))
      (node (ref "Q15") (pin "2") (pinfunction "GND_2") (pintype "bidirectional"))
      (node (ref "Q15") (pin "7") (pinfunction "REF1_7") (pintype "bidirectional"))
      (node (ref "Q17") (pin "2") (pinfunction "GND_2") (pintype "bidirectional"))
      (node (ref "Q17") (pin "7") (pinfunction "REF1_7") (pintype "bidirectional"))
      (node (ref "Q19") (pin "2") (pinfunction "GND_2") (pintype "bidirectional"))
      (node (ref "Q19") (pin "7") (pinfunction "REF1_7") (pintype "bidirectional"))
      (node (ref "Q2") (pin "2") (pinfunction "GND_2") (pintype "bidirectional"))
      (node (ref "Q2") (pin "7") (pinfunction "REF1_7") (pintype "bidirectional"))
      (node (ref "Q3") (pin "2") (pinfunction "GND_2") (pintype "bidirectional"))
      (node (ref "Q3") (pin "7") (pinfunction "REF1_7") (pintype "bidirectional"))
      (node (ref "Q4") (pin "5") (pinfunction "GND_5") (pintype "bidirectional"))
      (node (ref "Q5") (pin "5") (pinfunction "GND_5") (pintype "bidirectional"))
      (node (ref "Q8") (pin "2") (pinfunction "GND_2") (pintype "bidirectional"))
      (node (ref "Q8") (pin "7") (pinfunction "REF1_7") (pintype "bidirectional"))
      (node (ref "R4") (pin "1") (pinfunction "1_1") (pintype "passive"))
      (node (ref "R7") (pin "1") (pinfunction "1_1") (pintype "passive"))
      (node (ref "R8") (pin "1") (pinfunction "1_1") (pintype "passive"))
      (node (ref "SIDEOUS-12V") (pin "3") (pinfunction "-VIN_3") (pintype "bidirectional"))
      (node (ref "SIDEOUS-12V") (pin "4") (pinfunction "-VOUT_4") (pintype "bidirectional"))
      (node (ref "U$1") (pin "15") (pinfunction "GND_15") (pintype "bidirectional"))
      (node (ref "U$1") (pin "17") (pinfunction "GND_17") (pintype "bidirectional"))
      (node (ref "U$10") (pin "1") (pinfunction "GND_1") (pintype "bidirectional"))
      (node (ref "U$11") (pin "1") (pinfunction "GND_1") (pintype "bidirectional"))
      (node (ref "U$12") (pin "1") (pinfunction "GND_1") (pintype "bidirectional"))
      (node (ref "U$13") (pin "1") (pinfunction "GND_1") (pintype "bidirectional"))
      (node (ref "U$2") (pin "2") (pinfunction "A_2") (pintype "passive"))
      (node (ref "U$3") (pin "GND") (pinfunction "GND_GND") (pintype "bidirectional"))
      (node (ref "U$4") (pin "7") (pinfunction "7_7") (pintype "bidirectional"))
      (node (ref "U$4") (pin "8") (pinfunction "8_8") (pintype "bidirectional"))
      (node (ref "U$5") (pin "2") (pinfunction "A_2") (pintype "passive"))
      (node (ref "U$6") (pin "1") (pinfunction "GND_1") (pintype "bidirectional"))
      (node (ref "U$7") (pin "1") (pinfunction "GND_1") (pintype "bidirectional"))
      (node (ref "U$8") (pin "1") (pinfunction "GND_1") (pintype "bidirectional"))
      (node (ref "U$9") (pin "1") (pinfunction "GND_1") (pintype "bidirectional"))
      (node (ref "VADER-5V-EXT") (pin "1") (pinfunction "GND_1") (pintype "bidirectional"))
      (node (ref "VADER-5V-EXT") (pin "7") (pinfunction "GND1_7") (pintype "bidirectional"))
    )
    (net (code "14") (name "M1-IMEAS") (class "Default")
      (node (ref "Q1") (pin "5") (pinfunction "OUT_5") (pintype "bidirectional"))
      (node (ref "U$1") (pin "30") (pinfunction "D8/A8_30") (pintype "bidirectional"))
    )
    (net (code "15") (name "M1-SIG") (class "Default")
      (node (ref "U$1") (pin "27") (pinfunction "D5~{}_27") (pintype "bidirectional"))
      (node (ref "U$6") (pin "4") (pinfunction "IN_4") (pintype "bidirectional"))
    )
    (net (code "16") (name "M2-IMEAS") (class "Default")
      (node (ref "Q3") (pin "5") (pinfunction "OUT_5") (pintype "bidirectional"))
      (node (ref "U$1") (pin "29") (pinfunction "D9~{/A9}_29") (pintype "bidirectional"))
    )
    (net (code "17") (name "M2-SIG") (class "Default")
      (node (ref "U$1") (pin "26") (pinfunction "D13~{}_26") (pintype "bidirectional"))
      (node (ref "U$7") (pin "4") (pinfunction "IN_4") (pintype "bidirectional"))
    )
    (net (code "18") (name "M3-IMEAS") (class "Default")
      (node (ref "Q8") (pin "5") (pinfunction "OUT_5") (pintype "bidirectional"))
      (node (ref "U$1") (pin "28") (pinfunction "D10~{/A10}_28") (pintype "bidirectional"))
    )
    (net (code "19") (name "M3-SIG") (class "Default")
      (node (ref "U$1") (pin "25") (pinfunction "PE2_25") (pintype "bidirectional"))
      (node (ref "U$8") (pin "4") (pinfunction "IN_4") (pintype "bidirectional"))
    )
    (net (code "20") (name "M4-IMEAS") (class "Default")
      (node (ref "Q10") (pin "5") (pinfunction "OUT_5") (pintype "bidirectional"))
      (node (ref "U$1") (pin "24") (pinfunction "A0_24") (pintype "bidirectional"))
    )
    (net (code "21") (name "M4-SIG") (class "Default")
      (node (ref "U$1") (pin "5") (pinfunction "D2_5") (pintype "bidirectional"))
      (node (ref "U$9") (pin "4") (pinfunction "IN_4") (pintype "bidirectional"))
    )
    (net (code "22") (name "M5-IMEAS") (class "Default")
      (node (ref "Q13") (pin "5") (pinfunction "OUT_5") (pintype "bidirectional"))
      (node (ref "U$1") (pin "23") (pinfunction "A1_23") (pintype "bidirectional"))
    )
    (net (code "23") (name "M5-SIG") (class "Default")
      (node (ref "U$1") (pin "6") (pinfunction "D3~{}_6") (pintype "bidirectional"))
      (node (ref "U$10") (pin "4") (pinfunction "IN_4") (pintype "bidirectional"))
    )
    (net (code "24") (name "M6-IMEAS") (class "Default")
      (node (ref "Q15") (pin "5") (pinfunction "OUT_5") (pintype "bidirectional"))
      (node (ref "U$1") (pin "22") (pinfunction "A2_22") (pintype "bidirectional"))
    )
    (net (code "25") (name "M6-SIG") (class "Default")
      (node (ref "U$1") (pin "8") (pinfunction "D11~{}_8") (pintype "bidirectional"))
      (node (ref "U$11") (pin "4") (pinfunction "IN_4") (pintype "bidirectional"))
    )
    (net (code "26") (name "Net-(C20-Pad1)") (class "Default")
      (node (ref "C20") (pin "1") (pinfunction "1_1") (pintype "passive"))
      (node (ref "L2") (pin "5") (pinfunction "5_5") (pintype "bidirectional"))
      (node (ref "L2") (pin "6") (pinfunction "6_6") (pintype "bidirectional"))
      (node (ref "L2") (pin "7") (pinfunction "7_7") (pintype "bidirectional"))
      (node (ref "L2") (pin "8") (pinfunction "8_8") (pintype "bidirectional"))
      (node (ref "R2") (pin "1") (pinfunction "1_1") (pintype "passive"))
    )
    (net (code "27") (name "Net-(DOOKU-12V-CRIT-ADJUST)") (class "Default")
      (node (ref "DOOKU-12V-CRIT") (pin "4") (pinfunction "ADJUST_4") (pintype "bidirectional"))
      (node (ref "R7") (pin "2") (pinfunction "2_2") (pintype "passive"))
    )
    (net (code "28") (name "Net-(DOOKU-12V-CRIT-SENSE)") (class "Default")
      (node (ref "C21") (pin "+") (pinfunction "+_+") (pintype "passive"))
      (node (ref "DOOKU-12V-CRIT") (pin "5") (pinfunction "SENSE_5") (pintype "bidirectional"))
      (node (ref "DOOKU-12V-CRIT") (pin "6") (pinfunction "VOUT_6") (pintype "bidirectional"))
      (node (ref "L1") (pin "1") (pinfunction "1_1") (pintype "bidirectional"))
      (node (ref "L1") (pin "2") (pinfunction "2_2") (pintype "bidirectional"))
      (node (ref "L1") (pin "3") (pinfunction "3_3") (pintype "bidirectional"))
      (node (ref "L1") (pin "4") (pinfunction "4_4") (pintype "bidirectional"))
    )
    (net (code "29") (name "Net-(DOOKU-12V-CRIT-VIN)") (class "Default")
      (node (ref "C14") (pin "2") (pinfunction "2_2") (pintype "passive"))
      (node (ref "DOOKU-12V-CRIT") (pin "2") (pinfunction "VIN_2") (pintype "bidirectional"))
      (node (ref "L5") (pin "5") (pinfunction "5_5") (pintype "bidirectional"))
      (node (ref "L5") (pin "6") (pinfunction "6_6") (pintype "bidirectional"))
      (node (ref "L5") (pin "7") (pinfunction "7_7") (pintype "bidirectional"))
      (node (ref "L5") (pin "8") (pinfunction "8_8") (pintype "bidirectional"))
    )
    (net (code "30") (name "Net-(LED1-PadA)") (class "Default")
      (node (ref "LED1") (pin "A") (pinfunction "A_A") (pintype "passive"))
      (node (ref "R9") (pin "2") (pinfunction "2_2") (pintype "passive"))
    )
    (net (code "31") (name "Net-(LED2-PadA)") (class "Default")
      (node (ref "LED2") (pin "A") (pinfunction "A_A") (pintype "passive"))
      (node (ref "R10") (pin "2") (pinfunction "2_2") (pintype "passive"))
    )
    (net (code "32") (name "Net-(LED3-PadA)") (class "Default")
      (node (ref "LED3") (pin "A") (pinfunction "A_A") (pintype "passive"))
      (node (ref "R11") (pin "2") (pinfunction "2_2") (pintype "passive"))
    )
    (net (code "33") (name "Net-(LED4-PadA)") (class "Default")
      (node (ref "LED4") (pin "A") (pinfunction "A_A") (pintype "passive"))
      (node (ref "R12") (pin "2") (pinfunction "2_2") (pintype "passive"))
    )
    (net (code "34") (name "Net-(LED5-PadA)") (class "Default")
      (node (ref "LED5") (pin "A") (pinfunction "A_A") (pintype "passive"))
      (node (ref "R13") (pin "2") (pinfunction "2_2") (pintype "passive"))
    )
    (net (code "35") (name "Net-(LED6-PadA)") (class "Default")
      (node (ref "LED6") (pin "A") (pinfunction "A_A") (pintype "passive"))
      (node (ref "R16") (pin "2") (pinfunction "2_2") (pintype "passive"))
    )
    (net (code "36") (name "Net-(LED7-PadA)") (class "Default")
      (node (ref "LED7") (pin "A") (pinfunction "A_A") (pintype "passive"))
      (node (ref "R18") (pin "2") (pinfunction "2_2") (pintype "passive"))
    )
    (net (code "37") (name "Net-(LED8-PadA)") (class "Default")
      (node (ref "LED8") (pin "A") (pinfunction "A_A") (pintype "passive"))
      (node (ref "R20") (pin "2") (pinfunction "2_2") (pintype "passive"))
    )
    (net (code "38") (name "Net-(LED9-PadA)") (class "Default")
      (node (ref "LED9") (pin "A") (pinfunction "A_A") (pintype "passive"))
      (node (ref "R22") (pin "2") (pinfunction "2_2") (pintype "passive"))
    )
    (net (code "39") (name "Net-(LED10-PadA)") (class "Default")
      (node (ref "LED10") (pin "A") (pinfunction "A_A") (pintype "passive"))
      (node (ref "R24") (pin "2") (pinfunction "2_2") (pintype "passive"))
    )
    (net (code "40") (name "Net-(LED11-PadA)") (class "Default")
      (node (ref "LED11") (pin "A") (pinfunction "A_A") (pintype "passive"))
      (node (ref "R26") (pin "2") (pinfunction "2_2") (pintype "passive"))
    )
    (net (code "41") (name "Net-(LED12-PadA)") (class "Default")
      (node (ref "LED12") (pin "A") (pinfunction "A_A") (pintype "passive"))
      (node (ref "R28") (pin "2") (pinfunction "2_2") (pintype "passive"))
    )
    (net (code "42") (name "Net-(OKI-78SR-5/1.5-W36H-VO)") (class "Default")
      (node (ref "C17") (pin "1") (pinfunction "1_1") (pintype "passive"))
      (node (ref "L3") (pin "1") (pinfunction "1_1") (pintype "passive"))
      (node (ref "OKI-78SR-5/1.5-W36H") (pin "3") (pinfunction "VO_3") (pintype "bidirectional"))
    )
    (net (code "43") (name "Net-(PALPATINE-12V-+VIN)") (class "Default")
      (node (ref "L7") (pin "5") (pinfunction "5_5") (pintype "bidirectional"))
      (node (ref "L7") (pin "6") (pinfunction "6_6") (pintype "bidirectional"))
      (node (ref "L7") (pin "7") (pinfunction "7_7") (pintype "bidirectional"))
      (node (ref "L7") (pin "8") (pinfunction "8_8") (pintype "bidirectional"))
      (node (ref "PALPATINE-12V") (pin "1") (pinfunction "+VIN_1") (pintype "bidirectional"))
    )
    (net (code "44") (name "Net-(PALPATINE-12V-+VOUT)") (class "Default")
      (node (ref "C19") (pin "1") (pinfunction "1_1") (pintype "passive"))
      (node (ref "L2") (pin "1") (pinfunction "1_1") (pintype "bidirectional"))
      (node (ref "L2") (pin "2") (pinfunction "2_2") (pintype "bidirectional"))
      (node (ref "L2") (pin "3") (pinfunction "3_3") (pintype "bidirectional"))
      (node (ref "L2") (pin "4") (pinfunction "4_4") (pintype "bidirectional"))
      (node (ref "PALPATINE-12V") (pin "8") (pinfunction "+VOUT_8") (pintype "bidirectional"))
      (node (ref "SIDEOUS-12V") (pin "8") (pinfunction "+VOUT_8") (pintype "bidirectional"))
    )
    (net (code "45") (name "Net-(PALPATINE-12V-REMOTE)") (class "Default")
      (node (ref "PALPATINE-12V") (pin "2") (pinfunction "REMOTE_2") (pintype "bidirectional"))
      (node (ref "Q12") (pin "3") (pinfunction "D_3") (pintype "passive"))
      (node (ref "SIDEOUS-12V") (pin "2") (pinfunction "REMOTE_2") (pintype "bidirectional"))
    )
    (net (code "46") (name "Net-(Q1-+IN)") (class "Default")
      (node (ref "Q1") (pin "8") (pinfunction "+IN_8") (pintype "bidirectional"))
      (node (ref "R1") (pin "SENSE2") (pinfunction "SENSE2_SENSE2") (pintype "bidirectional"))
    )
    (net (code "47") (name "Net-(Q1--IN)") (class "Default")
      (node (ref "Q1") (pin "1") (pinfunction "-IN_1") (pintype "bidirectional"))
      (node (ref "R1") (pin "SENSE1") (pinfunction "SENSE1_SENSE1") (pintype "bidirectional"))
    )
    (net (code "48") (name "Net-(Q2-+IN)") (class "Default")
      (node (ref "Q2") (pin "8") (pinfunction "+IN_8") (pintype "bidirectional"))
      (node (ref "R2") (pin "SENSE2") (pinfunction "SENSE2_SENSE2") (pintype "bidirectional"))
    )
    (net (code "49") (name "Net-(Q2--IN)") (class "Default")
      (node (ref "Q2") (pin "1") (pinfunction "-IN_1") (pintype "bidirectional"))
      (node (ref "R2") (pin "SENSE1") (pinfunction "SENSE1_SENSE1") (pintype "bidirectional"))
    )
    (net (code "50") (name "Net-(Q3-+IN)") (class "Default")
      (node (ref "Q3") (pin "8") (pinfunction "+IN_8") (pintype "bidirectional"))
      (node (ref "R14") (pin "SENSE2") (pinfunction "SENSE2_SENSE2") (pintype "bidirectional"))
    )
    (net (code "51") (name "Net-(Q3--IN)") (class "Default")
      (node (ref "Q3") (pin "1") (pinfunction "-IN_1") (pintype "bidirectional"))
      (node (ref "R14") (pin "SENSE1") (pinfunction "SENSE1_SENSE1") (pintype "bidirectional"))
    )
    (net (code "52") (name "Net-(Q4-IP+)") (class "Default")
      (node (ref "C11") (pin "1") (pinfunction "1_1") (pintype "passive"))
      (node (ref "L4") (pin "5") (pinfunction "5_5") (pintype "bidirectional"))
      (node (ref "L4") (pin "6") (pinfunction "6_6") (pintype "bidirectional"))
      (node (ref "L4") (pin "7") (pinfunction "7_7") (pintype "bidirectional"))
      (node (ref "L4") (pin "8") (pinfunction "8_8") (pintype "bidirectional"))
      (node (ref "Q4") (pin "1") (pinfunction "IP+_1") (pintype "bidirectional"))
      (node (ref "U$2") (pin "1") (pinfunction "C_1") (pintype "passive"))
    )
    (net (code "53") (name "Net-(Q5-IP-)") (class "Default")
      (node (ref "C9") (pin "1") (pinfunction "1_1") (pintype "passive"))
      (node (ref "L1") (pin "5") (pinfunction "5_5") (pintype "bidirectional"))
      (node (ref "L1") (pin "6") (pinfunction "6_6") (pintype "bidirectional"))
      (node (ref "L1") (pin "7") (pinfunction "7_7") (pintype "bidirectional"))
      (node (ref "L1") (pin "8") (pinfunction "8_8") (pintype "bidirectional"))
      (node (ref "Q5") (pin "4") (pinfunction "IP-_4") (pintype "bidirectional"))
      (node (ref "U$5") (pin "1") (pinfunction "C_1") (pintype "passive"))
    )
    (net (code "54") (name "Net-(Q6-D)") (class "Default")
      (node (ref "C16") (pin "2") (pinfunction "2_2") (pintype "passive"))
      (node (ref "Q6") (pin "TAB") (pinfunction "D_TAB") (pintype "bidirectional"))
      (node (ref "R1") (pin "2") (pinfunction "2_2") (pintype "passive"))
      (node (ref "U$6") (pin "6") (pinfunction "SENSE_6") (pintype "bidirectional"))
      (node (ref "U$6") (pin "8") (pinfunction "V+_8") (pintype "bidirectional"))
    )
    (net (code "55") (name "Net-(Q6-G)") (class "Default")
      (node (ref "Q6") (pin "1") (pinfunction "G_1") (pintype "bidirectional"))
      (node (ref "U$6") (pin "5") (pinfunction "GATE_5") (pintype "bidirectional"))
    )
    (net (code "56") (name "Net-(Q6-S)") (class "Default")
      (node (ref "MOTOR_1") (pin "R1") (pinfunction "R_R1") (pintype "bidirectional"))
      (node (ref "MOTOR_1") (pin "R2") (pinfunction "R_R2") (pintype "bidirectional"))
      (node (ref "Q6") (pin "2") (pinfunction "S_2") (pintype "bidirectional"))
      (node (ref "R9") (pin "1") (pinfunction "1_1") (pintype "passive"))
    )
    (net (code "57") (name "Net-(Q7-D)") (class "Default")
      (node (ref "C24") (pin "2") (pinfunction "2_2") (pintype "passive"))
      (node (ref "Q7") (pin "TAB") (pinfunction "D_TAB") (pintype "bidirectional"))
      (node (ref "R14") (pin "2") (pinfunction "2_2") (pintype "passive"))
      (node (ref "U$7") (pin "6") (pinfunction "SENSE_6") (pintype "bidirectional"))
      (node (ref "U$7") (pin "8") (pinfunction "V+_8") (pintype "bidirectional"))
    )
    (net (code "58") (name "Net-(Q7-G)") (class "Default")
      (node (ref "Q7") (pin "1") (pinfunction "G_1") (pintype "bidirectional"))
      (node (ref "U$7") (pin "5") (pinfunction "GATE_5") (pintype "bidirectional"))
    )
    (net (code "59") (name "Net-(Q7-S)") (class "Default")
      (node (ref "MOTOR_2") (pin "R1") (pinfunction "R_R1") (pintype "bidirectional"))
      (node (ref "MOTOR_2") (pin "R2") (pinfunction "R_R2") (pintype "bidirectional"))
      (node (ref "Q7") (pin "2") (pinfunction "S_2") (pintype "bidirectional"))
      (node (ref "R16") (pin "1") (pinfunction "1_1") (pintype "passive"))
    )
    (net (code "60") (name "Net-(Q8-+IN)") (class "Default")
      (node (ref "Q8") (pin "8") (pinfunction "+IN_8") (pintype "bidirectional"))
      (node (ref "R17") (pin "SENSE2") (pinfunction "SENSE2_SENSE2") (pintype "bidirectional"))
    )
    (net (code "61") (name "Net-(Q8--IN)") (class "Default")
      (node (ref "Q8") (pin "1") (pinfunction "-IN_1") (pintype "bidirectional"))
      (node (ref "R17") (pin "SENSE1") (pinfunction "SENSE1_SENSE1") (pintype "bidirectional"))
    )
    (net (code "62") (name "Net-(Q9-D)") (class "Default")
      (node (ref "C26") (pin "2") (pinfunction "2_2") (pintype "passive"))
      (node (ref "Q9") (pin "TAB") (pinfunction "D_TAB") (pintype "bidirectional"))
      (node (ref "R17") (pin "2") (pinfunction "2_2") (pintype "passive"))
      (node (ref "U$8") (pin "6") (pinfunction "SENSE_6") (pintype "bidirectional"))
      (node (ref "U$8") (pin "8") (pinfunction "V+_8") (pintype "bidirectional"))
    )
    (net (code "63") (name "Net-(Q9-G)") (class "Default")
      (node (ref "Q9") (pin "1") (pinfunction "G_1") (pintype "bidirectional"))
      (node (ref "U$8") (pin "5") (pinfunction "GATE_5") (pintype "bidirectional"))
    )
    (net (code "64") (name "Net-(Q9-S)") (class "Default")
      (node (ref "MOTOR_3") (pin "R1") (pinfunction "R_R1") (pintype "bidirectional"))
      (node (ref "MOTOR_3") (pin "R2") (pinfunction "R_R2") (pintype "bidirectional"))
      (node (ref "Q9") (pin "2") (pinfunction "S_2") (pintype "bidirectional"))
      (node (ref "R18") (pin "1") (pinfunction "1_1") (pintype "passive"))
    )
    (net (code "65") (name "Net-(Q10-+IN)") (class "Default")
      (node (ref "Q10") (pin "8") (pinfunction "+IN_8") (pintype "bidirectional"))
      (node (ref "R19") (pin "SENSE2") (pinfunction "SENSE2_SENSE2") (pintype "bidirectional"))
    )
    (net (code "66") (name "Net-(Q10--IN)") (class "Default")
      (node (ref "Q10") (pin "1") (pinfunction "-IN_1") (pintype "bidirectional"))
      (node (ref "R19") (pin "SENSE1") (pinfunction "SENSE1_SENSE1") (pintype "bidirectional"))
    )
    (net (code "67") (name "Net-(Q11-D)") (class "Default")
      (node (ref "C28") (pin "2") (pinfunction "2_2") (pintype "passive"))
      (node (ref "Q11") (pin "TAB") (pinfunction "D_TAB") (pintype "bidirectional"))
      (node (ref "R19") (pin "2") (pinfunction "2_2") (pintype "passive"))
      (node (ref "U$9") (pin "6") (pinfunction "SENSE_6") (pintype "bidirectional"))
      (node (ref "U$9") (pin "8") (pinfunction "V+_8") (pintype "bidirectional"))
    )
    (net (code "68") (name "Net-(Q11-G)") (class "Default")
      (node (ref "Q11") (pin "1") (pinfunction "G_1") (pintype "bidirectional"))
      (node (ref "U$9") (pin "5") (pinfunction "GATE_5") (pintype "bidirectional"))
    )
    (net (code "69") (name "Net-(Q11-S)") (class "Default")
      (node (ref "MOTOR_4") (pin "R1") (pinfunction "R_R1") (pintype "bidirectional"))
      (node (ref "MOTOR_4") (pin "R2") (pinfunction "R_R2") (pintype "bidirectional"))
      (node (ref "Q11") (pin "2") (pinfunction "S_2") (pintype "bidirectional"))
      (node (ref "R20") (pin "1") (pinfunction "1_1") (pintype "passive"))
    )
    (net (code "70") (name "Net-(Q12-G)") (class "Default")
      (node (ref "Q12") (pin "1") (pinfunction "G_1") (pintype "passive"))
      (node (ref "R15") (pin "1") (pinfunction "1_1") (pintype "passive"))
    )
    (net (code "71") (name "Net-(Q13-+IN)") (class "Default")
      (node (ref "Q13") (pin "8") (pinfunction "+IN_8") (pintype "bidirectional"))
      (node (ref "R21") (pin "SENSE2") (pinfunction "SENSE2_SENSE2") (pintype "bidirectional"))
    )
    (net (code "72") (name "Net-(Q13--IN)") (class "Default")
      (node (ref "Q13") (pin "1") (pinfunction "-IN_1") (pintype "bidirectional"))
      (node (ref "R21") (pin "SENSE1") (pinfunction "SENSE1_SENSE1") (pintype "bidirectional"))
    )
    (net (code "73") (name "Net-(Q14-D)") (class "Default")
      (node (ref "C30") (pin "2") (pinfunction "2_2") (pintype "passive"))
      (node (ref "Q14") (pin "TAB") (pinfunction "D_TAB") (pintype "bidirectional"))
      (node (ref "R21") (pin "2") (pinfunction "2_2") (pintype "passive"))
      (node (ref "U$10") (pin "6") (pinfunction "SENSE_6") (pintype "bidirectional"))
      (node (ref "U$10") (pin "8") (pinfunction "V+_8") (pintype "bidirectional"))
    )
    (net (code "74") (name "Net-(Q14-G)") (class "Default")
      (node (ref "Q14") (pin "1") (pinfunction "G_1") (pintype "bidirectional"))
      (node (ref "U$10") (pin "5") (pinfunction "GATE_5") (pintype "bidirectional"))
    )
    (net (code "75") (name "Net-(Q14-S)") (class "Default")
      (node (ref "MOTOR_5") (pin "R1") (pinfunction "R_R1") (pintype "bidirectional"))
      (node (ref "MOTOR_5") (pin "R2") (pinfunction "R_R2") (pintype "bidirectional"))
      (node (ref "Q14") (pin "2") (pinfunction "S_2") (pintype "bidirectional"))
      (node (ref "R22") (pin "1") (pinfunction "1_1") (pintype "passive"))
    )
    (net (code "76") (name "Net-(Q15-+IN)") (class "Default")
      (node (ref "Q15") (pin "8") (pinfunction "+IN_8") (pintype "bidirectional"))
      (node (ref "R23") (pin "SENSE2") (pinfunction "SENSE2_SENSE2") (pintype "bidirectional"))
    )
    (net (code "77") (name "Net-(Q15--IN)") (class "Default")
      (node (ref "Q15") (pin "1") (pinfunction "-IN_1") (pintype "bidirectional"))
      (node (ref "R23") (pin "SENSE1") (pinfunction "SENSE1_SENSE1") (pintype "bidirectional"))
    )
    (net (code "78") (name "Net-(Q16-D)") (class "Default")
      (node (ref "C32") (pin "2") (pinfunction "2_2") (pintype "passive"))
      (node (ref "Q16") (pin "TAB") (pinfunction "D_TAB") (pintype "bidirectional"))
      (node (ref "R23") (pin "2") (pinfunction "2_2") (pintype "passive"))
      (node (ref "U$11") (pin "6") (pinfunction "SENSE_6") (pintype "bidirectional"))
      (node (ref "U$11") (pin "8") (pinfunction "V+_8") (pintype "bidirectional"))
    )
    (net (code "79") (name "Net-(Q16-G)") (class "Default")
      (node (ref "Q16") (pin "1") (pinfunction "G_1") (pintype "bidirectional"))
      (node (ref "U$11") (pin "5") (pinfunction "GATE_5") (pintype "bidirectional"))
    )
    (net (code "80") (name "Net-(Q16-S)") (class "Default")
      (node (ref "MOTOR_6") (pin "R1") (pinfunction "R_R1") (pintype "bidirectional"))
      (node (ref "MOTOR_6") (pin "R2") (pinfunction "R_R2") (pintype "bidirectional"))
      (node (ref "Q16") (pin "2") (pinfunction "S_2") (pintype "bidirectional"))
      (node (ref "R24") (pin "1") (pinfunction "1_1") (pintype "passive"))
    )
    (net (code "81") (name "Net-(Q17-+IN)") (class "Default")
      (node (ref "Q17") (pin "8") (pinfunction "+IN_8") (pintype "bidirectional"))
      (node (ref "R25") (pin "SENSE2") (pinfunction "SENSE2_SENSE2") (pintype "bidirectional"))
    )
    (net (code "82") (name "Net-(Q17--IN)") (class "Default")
      (node (ref "Q17") (pin "1") (pinfunction "-IN_1") (pintype "bidirectional"))
      (node (ref "R25") (pin "SENSE1") (pinfunction "SENSE1_SENSE1") (pintype "bidirectional"))
    )
    (net (code "83") (name "Net-(Q18-D)") (class "Default")
      (node (ref "C34") (pin "2") (pinfunction "2_2") (pintype "passive"))
      (node (ref "Q18") (pin "TAB") (pinfunction "D_TAB") (pintype "bidirectional"))
      (node (ref "R25") (pin "2") (pinfunction "2_2") (pintype "passive"))
      (node (ref "U$12") (pin "6") (pinfunction "SENSE_6") (pintype "bidirectional"))
      (node (ref "U$12") (pin "8") (pinfunction "V+_8") (pintype "bidirectional"))
    )
    (net (code "84") (name "Net-(Q18-G)") (class "Default")
      (node (ref "Q18") (pin "1") (pinfunction "G_1") (pintype "bidirectional"))
      (node (ref "U$12") (pin "5") (pinfunction "GATE_5") (pintype "bidirectional"))
    )
    (net (code "85") (name "Net-(Q18-S)") (class "Default")
      (node (ref "ARM_P") (pin "R1") (pinfunction "R_R1") (pintype "bidirectional"))
      (node (ref "ARM_P") (pin "R2") (pinfunction "R_R2") (pintype "bidirectional"))
      (node (ref "Q18") (pin "2") (pinfunction "S_2") (pintype "bidirectional"))
      (node (ref "R26") (pin "1") (pinfunction "1_1") (pintype "passive"))
    )
    (net (code "86") (name "Net-(Q19-+IN)") (class "Default")
      (node (ref "Q19") (pin "8") (pinfunction "+IN_8") (pintype "bidirectional"))
      (node (ref "R27") (pin "SENSE2") (pinfunction "SENSE2_SENSE2") (pintype "bidirectional"))
    )
    (net (code "87") (name "Net-(Q19--IN)") (class "Default")
      (node (ref "Q19") (pin "1") (pinfunction "-IN_1") (pintype "bidirectional"))
      (node (ref "R27") (pin "SENSE1") (pinfunction "SENSE1_SENSE1") (pintype "bidirectional"))
    )
    (net (code "88") (name "Net-(Q20-D)") (class "Default")
      (node (ref "C36") (pin "2") (pinfunction "2_2") (pintype "passive"))
      (node (ref "Q20") (pin "TAB") (pinfunction "D_TAB") (pintype "bidirectional"))
      (node (ref "R27") (pin "2") (pinfunction "2_2") (pintype "passive"))
      (node (ref "U$13") (pin "6") (pinfunction "SENSE_6") (pintype "bidirectional"))
      (node (ref "U$13") (pin "8") (pinfunction "V+_8") (pintype "bidirectional"))
    )
    (net (code "89") (name "Net-(Q20-G)") (class "Default")
      (node (ref "Q20") (pin "1") (pinfunction "G_1") (pintype "bidirectional"))
      (node (ref "U$13") (pin "5") (pinfunction "GATE_5") (pintype "bidirectional"))
    )
    (net (code "90") (name "Net-(Q20-S)") (class "Default")
      (node (ref "AUX_P") (pin "R1") (pinfunction "R_R1") (pintype "bidirectional"))
      (node (ref "AUX_P") (pin "R2") (pinfunction "R_R2") (pintype "bidirectional"))
      (node (ref "Q20") (pin "2") (pinfunction "S_2") (pintype "bidirectional"))
      (node (ref "R28") (pin "1") (pinfunction "1_1") (pintype "passive"))
    )
    (net (code "91") (name "Net-(R5-Pad1)") (class "Default")
      (node (ref "R5") (pin "1") (pinfunction "1_1") (pintype "passive"))
      (node (ref "U$3") (pin "A") (pinfunction "A_A") (pintype "bidirectional"))
      (node (ref "U$4") (pin "3") (pinfunction "3_3") (pintype "bidirectional"))
    )
    (net (code "92") (name "Net-(R5-Pad2)") (class "Default")
      (node (ref "R5") (pin "2") (pinfunction "2_2") (pintype "passive"))
      (node (ref "U$3") (pin "B") (pinfunction "B_B") (pintype "bidirectional"))
      (node (ref "U$4") (pin "6") (pinfunction "6_6") (pintype "bidirectional"))
    )
    (net (code "93") (name "Net-(R6-Pad1)") (class "Default")
      (node (ref "R6") (pin "1") (pinfunction "1_1") (pintype "passive"))
      (node (ref "U$3") (pin "Z") (pinfunction "Z_Z") (pintype "bidirectional"))
      (node (ref "U$4") (pin "2") (pinfunction "2_2") (pintype "bidirectional"))
    )
    (net (code "94") (name "Net-(R6-Pad2)") (class "Default")
      (node (ref "R6") (pin "2") (pinfunction "2_2") (pintype "passive"))
      (node (ref "U$3") (pin "Y") (pinfunction "Y_Y") (pintype "bidirectional"))
      (node (ref "U$4") (pin "1") (pinfunction "1_1") (pintype "bidirectional"))
    )
    (net (code "95") (name "Net-(SIDEOUS-12V-+VIN)") (class "Default")
      (node (ref "L6") (pin "5") (pinfunction "5_5") (pintype "bidirectional"))
      (node (ref "L6") (pin "6") (pinfunction "6_6") (pintype "bidirectional"))
      (node (ref "L6") (pin "7") (pinfunction "7_7") (pintype "bidirectional"))
      (node (ref "L6") (pin "8") (pinfunction "8_8") (pintype "bidirectional"))
      (node (ref "SIDEOUS-12V") (pin "1") (pinfunction "+VIN_1") (pintype "bidirectional"))
    )
    (net (code "96") (name "Net-(U$1-D0{slash}RX)") (class "Default")
      (node (ref "U$1") (pin "4") (pinfunction "D0/RX_4") (pintype "bidirectional"))
      (node (ref "U$3") (pin "RO") (pinfunction "R0_RO") (pintype "bidirectional"))
    )
    (net (code "97") (name "Net-(U$1-D1{slash}TX)") (class "Default")
      (node (ref "U$1") (pin "3") (pinfunction "D1/TX_3") (pintype "bidirectional"))
      (node (ref "U$3") (pin "DI") (pinfunction "DI_DI") (pintype "bidirectional"))
    )
    (net (code "98") (name "Net-(VADER-5V-EXT-ADJUST)") (class "Default")
      (node (ref "R8") (pin "2") (pinfunction "2_2") (pintype "passive"))
      (node (ref "VADER-5V-EXT") (pin "4") (pinfunction "ADJUST_4") (pintype "bidirectional"))
    )
    (net (code "99") (name "Net-(VADER-5V-EXT-SENSE)") (class "Default")
      (node (ref "C22") (pin "+") (pinfunction "+_+") (pintype "passive"))
      (node (ref "L4") (pin "1") (pinfunction "1_1") (pintype "bidirectional"))
      (node (ref "L4") (pin "2") (pinfunction "2_2") (pintype "bidirectional"))
      (node (ref "L4") (pin "3") (pinfunction "3_3") (pintype "bidirectional"))
      (node (ref "L4") (pin "4") (pinfunction "4_4") (pintype "bidirectional"))
      (node (ref "VADER-5V-EXT") (pin "5") (pinfunction "SENSE_5") (pintype "bidirectional"))
      (node (ref "VADER-5V-EXT") (pin "6") (pinfunction "VOUT_6") (pintype "bidirectional"))
    )
    (net (code "100") (name "Net-(VADER-5V-EXT-VIN)") (class "Default")
      (node (ref "C13") (pin "2") (pinfunction "2_2") (pintype "passive"))
      (node (ref "L8") (pin "5") (pinfunction "5_5") (pintype "bidirectional"))
      (node (ref "L8") (pin "6") (pinfunction "6_6") (pintype "bidirectional"))
      (node (ref "L8") (pin "7") (pinfunction "7_7") (pintype "bidirectional"))
      (node (ref "L8") (pin "8") (pinfunction "8_8") (pintype "bidirectional"))
      (node (ref "VADER-5V-EXT") (pin "2") (pinfunction "VIN_2") (pintype "bidirectional"))
    )
    (net (code "101") (name "PRIMARY-VMEAS") (class "Default")
      (node (ref "R3") (pin "1") (pinfunction "1_1") (pintype "passive"))
      (node (ref "R4") (pin "2") (pinfunction "2_2") (pintype "passive"))
      (node (ref "U$1") (pin "19") (pinfunction "A5_19") (pintype "bidirectional"))
    )
    (net (code "102") (name "V_BATT") (class "Default")
      (node (ref "BATT-POS") (pin "P$1") (pinfunction "P$1_P$1") (pintype "bidirectional"))
      (node (ref "C1") (pin "+") (pinfunction "+_+") (pintype "passive"))
      (node (ref "C10") (pin "2") (pinfunction "2_2") (pintype "passive"))
      (node (ref "C15") (pin "2") (pinfunction "2_2") (pintype "passive"))
      (node (ref "C2") (pin "+") (pinfunction "+_+") (pintype "passive"))
      (node (ref "C3") (pin "+") (pinfunction "+_+") (pintype "passive"))
      (node (ref "C4") (pin "+") (pinfunction "+_+") (pintype "passive"))
      (node (ref "L5") (pin "1") (pinfunction "1_1") (pintype "bidirectional"))
      (node (ref "L5") (pin "2") (pinfunction "2_2") (pintype "bidirectional"))
      (node (ref "L5") (pin "3") (pinfunction "3_3") (pintype "bidirectional"))
      (node (ref "L5") (pin "4") (pinfunction "4_4") (pintype "bidirectional"))
      (node (ref "L6") (pin "1") (pinfunction "1_1") (pintype "bidirectional"))
      (node (ref "L6") (pin "2") (pinfunction "2_2") (pintype "bidirectional"))
      (node (ref "L6") (pin "3") (pinfunction "3_3") (pintype "bidirectional"))
      (node (ref "L6") (pin "4") (pinfunction "4_4") (pintype "bidirectional"))
      (node (ref "L7") (pin "1") (pinfunction "1_1") (pintype "bidirectional"))
      (node (ref "L7") (pin "2") (pinfunction "2_2") (pintype "bidirectional"))
      (node (ref "L7") (pin "3") (pinfunction "3_3") (pintype "bidirectional"))
      (node (ref "L7") (pin "4") (pinfunction "4_4") (pintype "bidirectional"))
      (node (ref "L8") (pin "1") (pinfunction "1_1") (pintype "bidirectional"))
      (node (ref "L8") (pin "2") (pinfunction "2_2") (pintype "bidirectional"))
      (node (ref "L8") (pin "3") (pinfunction "3_3") (pintype "bidirectional"))
      (node (ref "L8") (pin "4") (pinfunction "4_4") (pintype "bidirectional"))
      (node (ref "R1") (pin "1") (pinfunction "1_1") (pintype "passive"))
      (node (ref "R14") (pin "1") (pinfunction "1_1") (pintype "passive"))
      (node (ref "R17") (pin "1") (pinfunction "1_1") (pintype "passive"))
      (node (ref "R19") (pin "1") (pinfunction "1_1") (pintype "passive"))
      (node (ref "R21") (pin "1") (pinfunction "1_1") (pintype "passive"))
      (node (ref "R23") (pin "1") (pinfunction "1_1") (pintype "passive"))
      (node (ref "R25") (pin "1") (pinfunction "1_1") (pintype "passive"))
      (node (ref "R27") (pin "1") (pinfunction "1_1") (pintype "passive"))
      (node (ref "R3") (pin "2") (pinfunction "2_2") (pintype "passive"))
    )
    (net (code "103") (name "unconnected-(DOOKU-12V-CRIT-INHIBIT-Pad3)") (class "Default")
      (node (ref "DOOKU-12V-CRIT") (pin "3") (pinfunction "INHIBIT_3") (pintype "bidirectional"))
    )
    (net (code "104") (name "unconnected-(Q4-FAULT-Pad6)") (class "Default")
      (node (ref "Q4") (pin "6") (pinfunction "FAULT_6") (pintype "bidirectional"))
    )
    (net (code "105") (name "unconnected-(Q5-FAULT-Pad6)") (class "Default")
      (node (ref "Q5") (pin "6") (pinfunction "FAULT_6") (pintype "bidirectional"))
    )
    (net (code "106") (name "unconnected-(U$1-AREF-Pad18)") (class "Default")
      (node (ref "U$1") (pin "18") (pinfunction "AREF_18") (pintype "bidirectional"))
    )
    (net (code "107") (name "unconnected-(U$1-MISO-Pad9)") (class "Default")
      (node (ref "U$1") (pin "9") (pinfunction "MISO_9") (pintype "bidirectional"))
    )
    (net (code "108") (name "unconnected-(U$1-MOSI-Pad10)") (class "Default")
      (node (ref "U$1") (pin "10") (pinfunction "MOSI_10") (pintype "bidirectional"))
    )
    (net (code "109") (name "unconnected-(U$1-RST-Pad7)") (class "Default")
      (node (ref "U$1") (pin "7") (pinfunction "RST_7") (pintype "bidirectional"))
    )
    (net (code "110") (name "unconnected-(U$1-SCK-Pad11)") (class "Default")
      (node (ref "U$1") (pin "11") (pinfunction "SCK_11") (pintype "bidirectional"))
    )
    (net (code "111") (name "unconnected-(U$1-VBUS-Pad16)") (class "Default")
      (node (ref "U$1") (pin "16") (pinfunction "VBUS_16") (pintype "bidirectional"))
    )
    (net (code "112") (name "unconnected-(U$4-Pad4)") (class "Default")
      (node (ref "U$4") (pin "4") (pinfunction "4_4") (pintype "bidirectional"))
    )
    (net (code "113") (name "unconnected-(U$4-Pad5)") (class "Default")
      (node (ref "U$4") (pin "5") (pinfunction "5_5") (pintype "bidirectional"))
    )
    (net (code "114") (name "unconnected-(U$6-FAULT-Pad3)") (class "Default")
      (node (ref "U$6") (pin "3") (pinfunction "FAULT_3") (pintype "bidirectional"))
    )
    (net (code "115") (name "unconnected-(U$6-TIMER-Pad2)") (class "Default")
      (node (ref "U$6") (pin "2") (pinfunction "TIMER_2") (pintype "bidirectional"))
    )
    (net (code "116") (name "unconnected-(U$7-FAULT-Pad3)") (class "Default")
      (node (ref "U$7") (pin "3") (pinfunction "FAULT_3") (pintype "bidirectional"))
    )
    (net (code "117") (name "unconnected-(U$7-TIMER-Pad2)") (class "Default")
      (node (ref "U$7") (pin "2") (pinfunction "TIMER_2") (pintype "bidirectional"))
    )
    (net (code "118") (name "unconnected-(U$8-FAULT-Pad3)") (class "Default")
      (node (ref "U$8") (pin "3") (pinfunction "FAULT_3") (pintype "bidirectional"))
    )
    (net (code "119") (name "unconnected-(U$8-TIMER-Pad2)") (class "Default")
      (node (ref "U$8") (pin "2") (pinfunction "TIMER_2") (pintype "bidirectional"))
    )
    (net (code "120") (name "unconnected-(U$9-FAULT-Pad3)") (class "Default")
      (node (ref "U$9") (pin "3") (pinfunction "FAULT_3") (pintype "bidirectional"))
    )
    (net (code "121") (name "unconnected-(U$9-TIMER-Pad2)") (class "Default")
      (node (ref "U$9") (pin "2") (pinfunction "TIMER_2") (pintype "bidirectional"))
    )
    (net (code "122") (name "unconnected-(U$10-FAULT-Pad3)") (class "Default")
      (node (ref "U$10") (pin "3") (pinfunction "FAULT_3") (pintype "bidirectional"))
    )
    (net (code "123") (name "unconnected-(U$10-TIMER-Pad2)") (class "Default")
      (node (ref "U$10") (pin "2") (pinfunction "TIMER_2") (pintype "bidirectional"))
    )
    (net (code "124") (name "unconnected-(U$11-FAULT-Pad3)") (class "Default")
      (node (ref "U$11") (pin "3") (pinfunction "FAULT_3") (pintype "bidirectional"))
    )
    (net (code "125") (name "unconnected-(U$11-TIMER-Pad2)") (class "Default")
      (node (ref "U$11") (pin "2") (pinfunction "TIMER_2") (pintype "bidirectional"))
    )
    (net (code "126") (name "unconnected-(U$12-FAULT-Pad3)") (class "Default")
      (node (ref "U$12") (pin "3") (pinfunction "FAULT_3") (pintype "bidirectional"))
    )
    (net (code "127") (name "unconnected-(U$12-TIMER-Pad2)") (class "Default")
      (node (ref "U$12") (pin "2") (pinfunction "TIMER_2") (pintype "bidirectional"))
    )
    (net (code "128") (name "unconnected-(U$13-FAULT-Pad3)") (class "Default")
      (node (ref "U$13") (pin "3") (pinfunction "FAULT_3") (pintype "bidirectional"))
    )
    (net (code "129") (name "unconnected-(U$13-TIMER-Pad2)") (class "Default")
      (node (ref "U$13") (pin "2") (pinfunction "TIMER_2") (pintype "bidirectional"))
    )
    (net (code "130") (name "unconnected-(VADER-5V-EXT-INHIBIT-Pad3)") (class "Default")
      (node (ref "VADER-5V-EXT") (pin "3") (pinfunction "INHIBIT_3") (pintype "bidirectional"))
    )
  )
)
